# Bien_Quang_Cao_ver2_schematic.net
KiCad netlist of a schematic drawn in Altium Designer
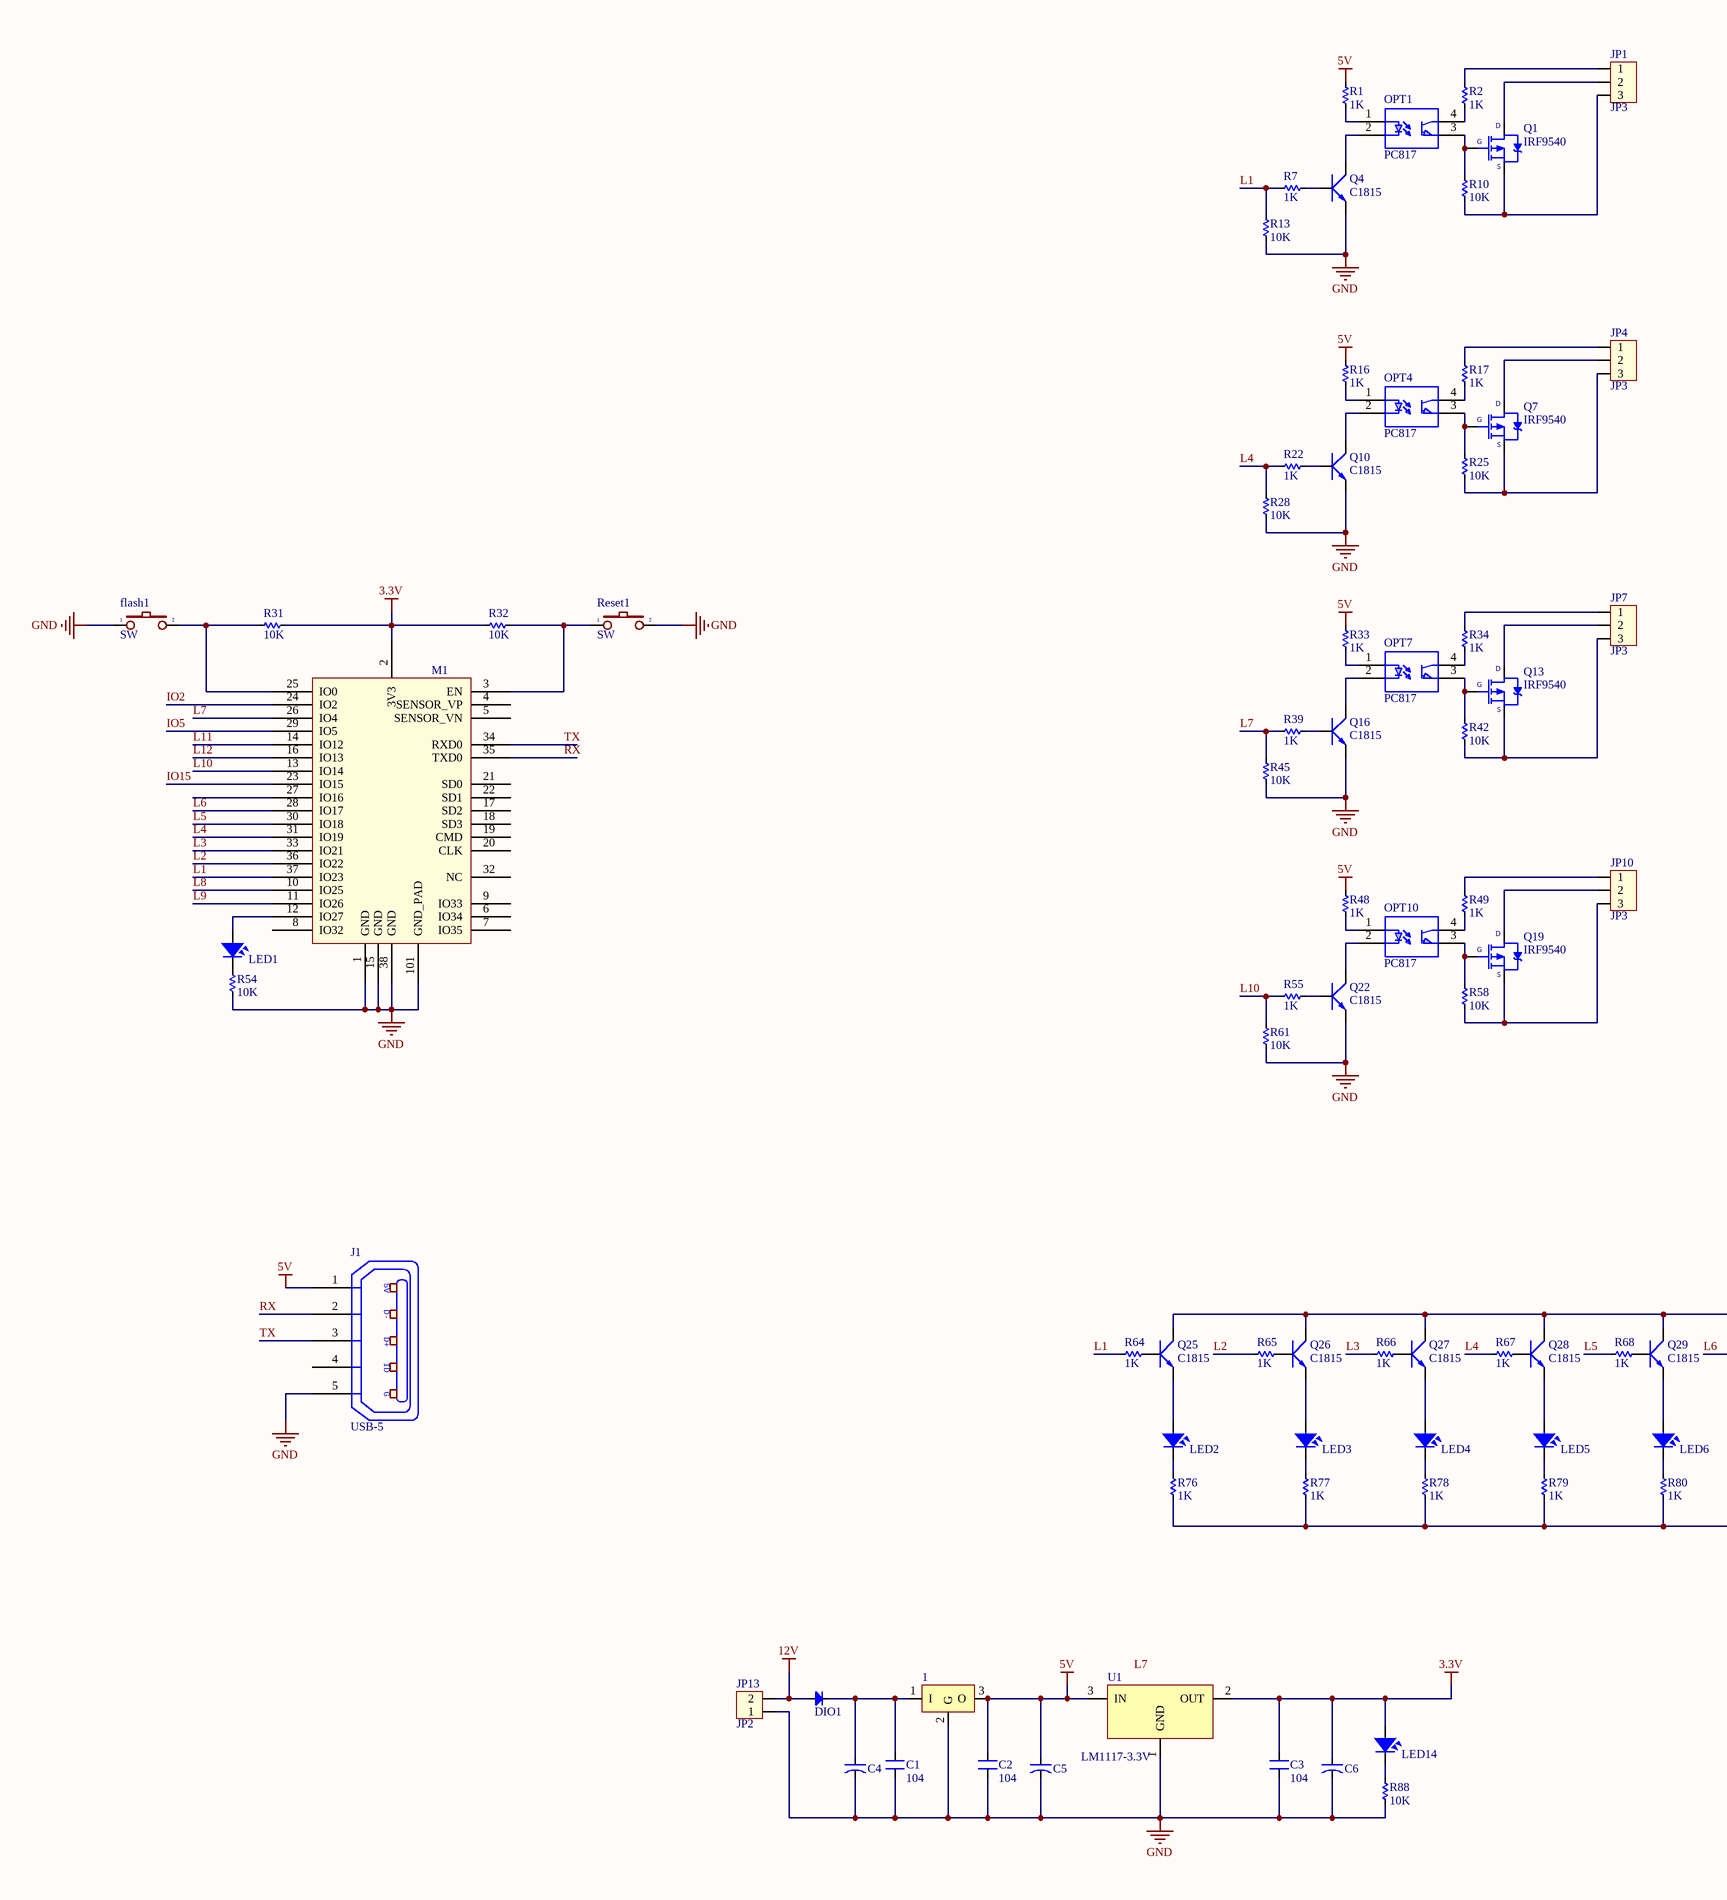
[diagram p0: Bien_Quang_Cao_ver2_schematic.SchDoc, left]
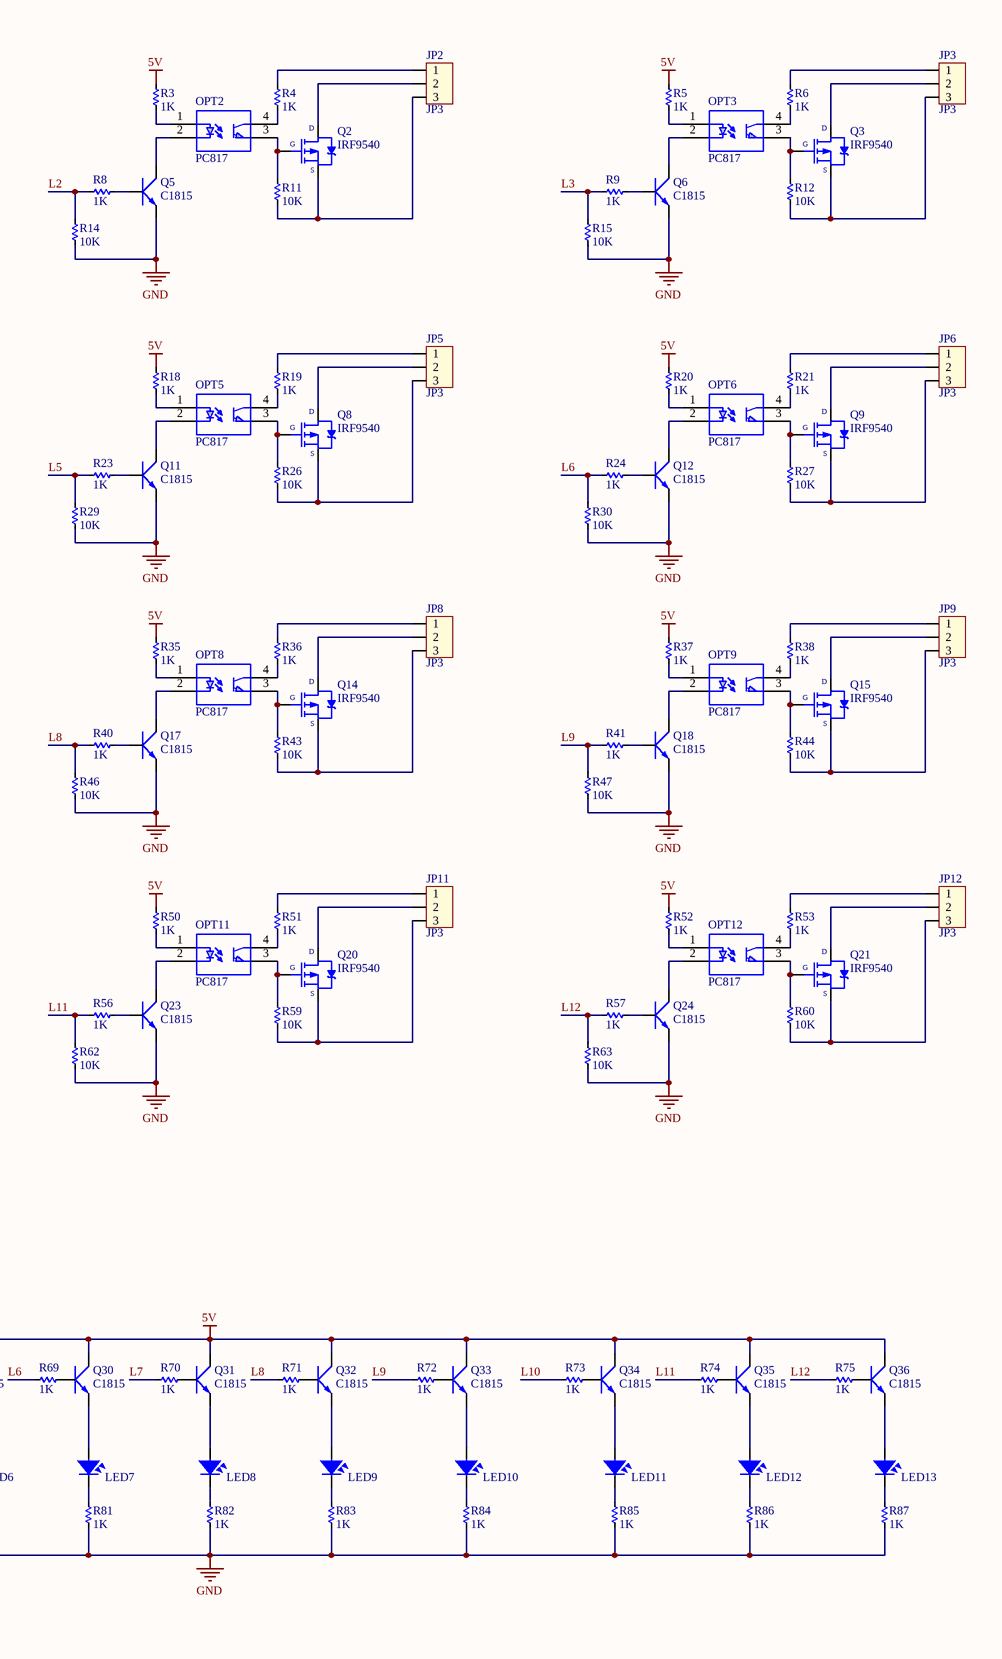
[diagram p1: Bien_Quang_Cao_ver2_schematic.SchDoc, right]

(export (version "E")
  (design (tool "Eeschema 10.0.6"))
  (components
    (comp (ref "1")
      (value "LM78xx")
      (footprint "TO252-123")
      (description "Positive Voltage Regulator")
      (fields (field (name "PUBLISHER") "Altium Limited"))
      (libsource (lib "LIBRARY") (part "LM78xx"))
    )
    (comp (ref "C1")
      (value "104")
      (footprint "SM-CAP-0805")
      (fields (field (name "DESIGNED BY") "VanDungEvn"))
      (libsource (lib "electronicvn-library1") (part "CN"))
    )
    (comp (ref "C2")
      (value "104")
      (footprint "SM-CAP-0805")
      (fields (field (name "DESIGNED BY") "VanDungEvn"))
      (libsource (lib "electronicvn-library1") (part "CN"))
    )
    (comp (ref "C3")
      (value "104")
      (footprint "SM-CAP-0805")
      (fields (field (name "DESIGNED BY") "VanDungEvn"))
      (libsource (lib "electronicvn-library1") (part "CN"))
    )
    (comp (ref "C4")
      (value "CN-ALU-SMD")
      (footprint "CAP-ALU-SMD-5x5.5x1.4")
      (description "Polarized Capacitor (Axial)")
      (fields (field (name "PUBLISHER") "Altium Limited"))
      (libsource (lib "LIBTanCN") (part "CN-ALU-SMD"))
    )
    (comp (ref "C5")
      (value "CN-ALU-SMD")
      (footprint "CAP-ALU-SMD-5x5.5x1.4")
      (description "Polarized Capacitor (Axial)")
      (fields (field (name "PUBLISHER") "Altium Limited"))
      (libsource (lib "LIBTanCN") (part "CN-ALU-SMD"))
    )
    (comp (ref "C6")
      (value "CN-ALU-SMD")
      (footprint "CAP-ALU-SMD-5x5.5x1.4")
      (description "Polarized Capacitor (Axial)")
      (fields (field (name "PUBLISHER") "Altium Limited"))
      (libsource (lib "LIBTanCN") (part "CN-ALU-SMD"))
    )
    (comp (ref "DIO1")
      (value "Diode SMD")
      (footprint "DIO-SMD-106")
      (description "Default Diode")
      (fields (field (name "PUBLISHER") "Altium Limited"))
      (libsource (lib "LIBRARY") (part "Diode SMD"))
    )
    (comp (ref "flash1")
      (value "SW")
      (footprint "SW-DIP1")
      (description "Switch button 2 pin")
      (libsource (lib "LIBRARY") (part "SW2"))
    )
    (comp (ref "J1")
      (value "USB-5")
      (footprint "USB-M1")
      (fields
        (field (name "MANUFACTURER") "FCI")
        (field (name "MANUFACTURER PART NUMBER") "10118193-0001LF")
        (field (name ".CREATOR") "MM")
        (field (name ".CHECKED PCB") "RF")
        (field (name ".CHECKED SCH") "MM")
      )
      (libsource (lib "LIBRARY") (part "USB-5"))
    )
    (comp (ref "JP1")
      (value "JP3")
      (footprint "CON 3/9.5mm - CHAN LECH")
      (description "Connector 3")
      (libsource (lib "Tr.Thoai") (part "Con3"))
    )
    (comp (ref "JP2")
      (value "JP3")
      (footprint "CON 3/9.5mm - CHAN LECH")
      (description "Connector 3")
      (libsource (lib "Tr.Thoai") (part "Con3"))
    )
    (comp (ref "JP3")
      (value "JP3")
      (footprint "CON 3/9.5mm - CHAN LECH")
      (description "Connector 3")
      (libsource (lib "Tr.Thoai") (part "Con3"))
    )
    (comp (ref "JP4")
      (value "JP3")
      (footprint "CON 3/9.5mm - CHAN LECH")
      (description "Connector 3")
      (libsource (lib "Tr.Thoai") (part "Con3"))
    )
    (comp (ref "JP5")
      (value "JP3")
      (footprint "CON 3/9.5mm - CHAN LECH")
      (description "Connector 3")
      (libsource (lib "Tr.Thoai") (part "Con3"))
    )
    (comp (ref "JP6")
      (value "JP3")
      (footprint "CON 3/9.5mm - CHAN LECH")
      (description "Connector 3")
      (libsource (lib "Tr.Thoai") (part "Con3"))
    )
    (comp (ref "JP7")
      (value "JP3")
      (footprint "CON 3/9.5mm - CHAN LECH")
      (description "Connector 3")
      (libsource (lib "Tr.Thoai") (part "Con3"))
    )
    (comp (ref "JP8")
      (value "JP3")
      (footprint "CON 3/9.5mm - CHAN LECH")
      (description "Connector 3")
      (libsource (lib "Tr.Thoai") (part "Con3"))
    )
    (comp (ref "JP9")
      (value "JP3")
      (footprint "CON 3/9.5mm - CHAN LECH")
      (description "Connector 3")
      (libsource (lib "Tr.Thoai") (part "Con3"))
    )
    (comp (ref "JP10")
      (value "JP3")
      (footprint "CON 3/9.5mm - CHAN LECH")
      (description "Connector 3")
      (libsource (lib "Tr.Thoai") (part "Con3"))
    )
    (comp (ref "JP11")
      (value "JP3")
      (footprint "CON 3/9.5mm - CHAN LECH")
      (description "Connector 3")
      (libsource (lib "Tr.Thoai") (part "Con3"))
    )
    (comp (ref "JP12")
      (value "JP3")
      (footprint "CON 3/9.5mm - CHAN LECH")
      (description "Connector 3")
      (libsource (lib "Tr.Thoai") (part "Con3"))
    )
    (comp (ref "JP13")
      (value "JP2")
      (footprint "CON 2/7.62mm")
      (description "Connector 2")
      (libsource (lib "Tr.Thoai") (part "Con2"))
    )
    (comp (ref "LED1") (value "LED") (footprint "LED-0805-Blue") (libsource (lib "LIBRARY") (part "LED SMD")))
    (comp (ref "LED2") (value "LED") (footprint "LED-0805-Blue") (libsource (lib "LIBRARY") (part "LED SMD")))
    (comp (ref "LED3") (value "LED") (footprint "LED-0805-Blue") (libsource (lib "LIBRARY") (part "LED SMD")))
    (comp (ref "LED4") (value "LED") (footprint "LED-0805-Blue") (libsource (lib "LIBRARY") (part "LED SMD")))
    (comp (ref "LED5") (value "LED") (footprint "LED-0805-Blue") (libsource (lib "LIBRARY") (part "LED SMD")))
    (comp (ref "LED6") (value "LED") (footprint "LED-0805-Blue") (libsource (lib "LIBRARY") (part "LED SMD")))
    (comp (ref "LED7") (value "LED") (footprint "LED-0805-Blue") (libsource (lib "LIBRARY") (part "LED SMD")))
    (comp (ref "LED8") (value "LED") (footprint "LED-0805-Blue") (libsource (lib "LIBRARY") (part "LED SMD")))
    (comp (ref "LED9") (value "LED") (footprint "LED-0805-Blue") (libsource (lib "LIBRARY") (part "LED SMD")))
    (comp (ref "LED10")
      (value "LED")
      (footprint "LED-0805-Blue")
      (libsource (lib "LIBRARY") (part "LED SMD"))
    )
    (comp (ref "LED11")
      (value "LED")
      (footprint "LED-0805-Blue")
      (libsource (lib "LIBRARY") (part "LED SMD"))
    )
    (comp (ref "LED12")
      (value "LED")
      (footprint "LED-0805-Blue")
      (libsource (lib "LIBRARY") (part "LED SMD"))
    )
    (comp (ref "LED13")
      (value "LED")
      (footprint "LED-0805-Blue")
      (libsource (lib "LIBRARY") (part "LED SMD"))
    )
    (comp (ref "LED14")
      (value "LED")
      (footprint "LED-0805-Blue")
      (libsource (lib "LIBRARY") (part "LED SMD"))
    )
    (comp (ref "M1")
      (value "ESP32S_Module")
      (footprint "ESP32S")
      (description "Esp-32S")
      (libsource (lib "ESP32S") (part "ESP32S_Module"))
    )
    (comp (ref "OPT1")
      (value "PC817")
      (footprint "DIP-4 SMD")
      (description "OptoAcoplador 4 terminais")
      (libsource (lib "Altium_Library_Brasil") (part "PC817"))
    )
    (comp (ref "OPT2")
      (value "PC817")
      (footprint "DIP-4 SMD")
      (description "OptoAcoplador 4 terminais")
      (libsource (lib "Altium_Library_Brasil") (part "PC817"))
    )
    (comp (ref "OPT3")
      (value "PC817")
      (footprint "DIP-4 SMD")
      (description "OptoAcoplador 4 terminais")
      (libsource (lib "Altium_Library_Brasil") (part "PC817"))
    )
    (comp (ref "OPT4")
      (value "PC817")
      (footprint "DIP-4 SMD")
      (description "OptoAcoplador 4 terminais")
      (libsource (lib "Altium_Library_Brasil") (part "PC817"))
    )
    (comp (ref "OPT5")
      (value "PC817")
      (footprint "DIP-4 SMD")
      (description "OptoAcoplador 4 terminais")
      (libsource (lib "Altium_Library_Brasil") (part "PC817"))
    )
    (comp (ref "OPT6")
      (value "PC817")
      (footprint "DIP-4 SMD")
      (description "OptoAcoplador 4 terminais")
      (libsource (lib "Altium_Library_Brasil") (part "PC817"))
    )
    (comp (ref "OPT7")
      (value "PC817")
      (footprint "DIP-4 SMD")
      (description "OptoAcoplador 4 terminais")
      (libsource (lib "Altium_Library_Brasil") (part "PC817"))
    )
    (comp (ref "OPT8")
      (value "PC817")
      (footprint "DIP-4 SMD")
      (description "OptoAcoplador 4 terminais")
      (libsource (lib "Altium_Library_Brasil") (part "PC817"))
    )
    (comp (ref "OPT9")
      (value "PC817")
      (footprint "DIP-4 SMD")
      (description "OptoAcoplador 4 terminais")
      (libsource (lib "Altium_Library_Brasil") (part "PC817"))
    )
    (comp (ref "OPT10")
      (value "PC817")
      (footprint "DIP-4 SMD")
      (description "OptoAcoplador 4 terminais")
      (libsource (lib "Altium_Library_Brasil") (part "PC817"))
    )
    (comp (ref "OPT11")
      (value "PC817")
      (footprint "DIP-4 SMD")
      (description "OptoAcoplador 4 terminais")
      (libsource (lib "Altium_Library_Brasil") (part "PC817"))
    )
    (comp (ref "OPT12")
      (value "PC817")
      (footprint "DIP-4 SMD")
      (description "OptoAcoplador 4 terminais")
      (libsource (lib "Altium_Library_Brasil") (part "PC817"))
    )
    (comp (ref "Q1")
      (value "IRF9540")
      (footprint "TO247")
      (description "HEXFET P-Channel Power MOSFET")
      (fields (field (name "PUBLISHER") "Altium Limited"))
      (libsource (lib "LIBTanCN") (part "IRF9540"))
    )
    (comp (ref "Q2")
      (value "IRF9540")
      (footprint "TO247")
      (description "HEXFET P-Channel Power MOSFET")
      (fields (field (name "PUBLISHER") "Altium Limited"))
      (libsource (lib "LIBTanCN") (part "IRF9540"))
    )
    (comp (ref "Q3")
      (value "IRF9540")
      (footprint "TO247")
      (description "HEXFET P-Channel Power MOSFET")
      (fields (field (name "PUBLISHER") "Altium Limited"))
      (libsource (lib "LIBTanCN") (part "IRF9540"))
    )
    (comp (ref "Q4")
      (value "C1815")
      (footprint "SOT23B")
      (description "NPN 600mW, ECB")
      (libsource (lib "electronicvn-library1") (part "C1815"))
    )
    (comp (ref "Q5")
      (value "C1815")
      (footprint "SOT23B")
      (description "NPN 600mW, ECB")
      (libsource (lib "electronicvn-library1") (part "C1815"))
    )
    (comp (ref "Q6")
      (value "C1815")
      (footprint "SOT23B")
      (description "NPN 600mW, ECB")
      (libsource (lib "electronicvn-library1") (part "C1815"))
    )
    (comp (ref "Q7")
      (value "IRF9540")
      (footprint "TO247")
      (description "HEXFET P-Channel Power MOSFET")
      (fields (field (name "PUBLISHER") "Altium Limited"))
      (libsource (lib "LIBTanCN") (part "IRF9540"))
    )
    (comp (ref "Q8")
      (value "IRF9540")
      (footprint "TO247")
      (description "HEXFET P-Channel Power MOSFET")
      (fields (field (name "PUBLISHER") "Altium Limited"))
      (libsource (lib "LIBTanCN") (part "IRF9540"))
    )
    (comp (ref "Q9")
      (value "IRF9540")
      (footprint "TO247")
      (description "HEXFET P-Channel Power MOSFET")
      (fields (field (name "PUBLISHER") "Altium Limited"))
      (libsource (lib "LIBTanCN") (part "IRF9540"))
    )
    (comp (ref "Q10")
      (value "C1815")
      (footprint "SOT23B")
      (description "NPN 600mW, ECB")
      (libsource (lib "electronicvn-library1") (part "C1815"))
    )
    (comp (ref "Q11")
      (value "C1815")
      (footprint "SOT23B")
      (description "NPN 600mW, ECB")
      (libsource (lib "electronicvn-library1") (part "C1815"))
    )
    (comp (ref "Q12")
      (value "C1815")
      (footprint "SOT23B")
      (description "NPN 600mW, ECB")
      (libsource (lib "electronicvn-library1") (part "C1815"))
    )
    (comp (ref "Q13")
      (value "IRF9540")
      (footprint "TO247")
      (description "HEXFET P-Channel Power MOSFET")
      (fields (field (name "PUBLISHER") "Altium Limited"))
      (libsource (lib "LIBTanCN") (part "IRF9540"))
    )
    (comp (ref "Q14")
      (value "IRF9540")
      (footprint "TO247")
      (description "HEXFET P-Channel Power MOSFET")
      (fields (field (name "PUBLISHER") "Altium Limited"))
      (libsource (lib "LIBTanCN") (part "IRF9540"))
    )
    (comp (ref "Q15")
      (value "IRF9540")
      (footprint "TO247")
      (description "HEXFET P-Channel Power MOSFET")
      (fields (field (name "PUBLISHER") "Altium Limited"))
      (libsource (lib "LIBTanCN") (part "IRF9540"))
    )
    (comp (ref "Q16")
      (value "C1815")
      (footprint "SOT23B")
      (description "NPN 600mW, ECB")
      (libsource (lib "electronicvn-library1") (part "C1815"))
    )
    (comp (ref "Q17")
      (value "C1815")
      (footprint "SOT23B")
      (description "NPN 600mW, ECB")
      (libsource (lib "electronicvn-library1") (part "C1815"))
    )
    (comp (ref "Q18")
      (value "C1815")
      (footprint "SOT23B")
      (description "NPN 600mW, ECB")
      (libsource (lib "electronicvn-library1") (part "C1815"))
    )
    (comp (ref "Q19")
      (value "IRF9540")
      (footprint "TO247")
      (description "HEXFET P-Channel Power MOSFET")
      (fields (field (name "PUBLISHER") "Altium Limited"))
      (libsource (lib "LIBTanCN") (part "IRF9540"))
    )
    (comp (ref "Q20")
      (value "IRF9540")
      (footprint "TO247")
      (description "HEXFET P-Channel Power MOSFET")
      (fields (field (name "PUBLISHER") "Altium Limited"))
      (libsource (lib "LIBTanCN") (part "IRF9540"))
    )
    (comp (ref "Q21")
      (value "IRF9540")
      (footprint "TO247")
      (description "HEXFET P-Channel Power MOSFET")
      (fields (field (name "PUBLISHER") "Altium Limited"))
      (libsource (lib "LIBTanCN") (part "IRF9540"))
    )
    (comp (ref "Q22")
      (value "C1815")
      (footprint "SOT23B")
      (description "NPN 600mW, ECB")
      (libsource (lib "electronicvn-library1") (part "C1815"))
    )
    (comp (ref "Q23")
      (value "C1815")
      (footprint "SOT23B")
      (description "NPN 600mW, ECB")
      (libsource (lib "electronicvn-library1") (part "C1815"))
    )
    (comp (ref "Q24")
      (value "C1815")
      (footprint "SOT23B")
      (description "NPN 600mW, ECB")
      (libsource (lib "electronicvn-library1") (part "C1815"))
    )
    (comp (ref "Q25")
      (value "C1815")
      (footprint "SOT23B")
      (description "NPN 600mW, ECB")
      (libsource (lib "electronicvn-library1") (part "C1815"))
    )
    (comp (ref "Q26")
      (value "C1815")
      (footprint "SOT23B")
      (description "NPN 600mW, ECB")
      (libsource (lib "electronicvn-library1") (part "C1815"))
    )
    (comp (ref "Q27")
      (value "C1815")
      (footprint "SOT23B")
      (description "NPN 600mW, ECB")
      (libsource (lib "electronicvn-library1") (part "C1815"))
    )
    (comp (ref "Q28")
      (value "C1815")
      (footprint "SOT23B")
      (description "NPN 600mW, ECB")
      (libsource (lib "electronicvn-library1") (part "C1815"))
    )
    (comp (ref "Q29")
      (value "C1815")
      (footprint "SOT23B")
      (description "NPN 600mW, ECB")
      (libsource (lib "electronicvn-library1") (part "C1815"))
    )
    (comp (ref "Q30")
      (value "C1815")
      (footprint "SOT23B")
      (description "NPN 600mW, ECB")
      (libsource (lib "electronicvn-library1") (part "C1815"))
    )
    (comp (ref "Q31")
      (value "C1815")
      (footprint "SOT23B")
      (description "NPN 600mW, ECB")
      (libsource (lib "electronicvn-library1") (part "C1815"))
    )
    (comp (ref "Q32")
      (value "C1815")
      (footprint "SOT23B")
      (description "NPN 600mW, ECB")
      (libsource (lib "electronicvn-library1") (part "C1815"))
    )
    (comp (ref "Q33")
      (value "C1815")
      (footprint "SOT23B")
      (description "NPN 600mW, ECB")
      (libsource (lib "electronicvn-library1") (part "C1815"))
    )
    (comp (ref "Q34")
      (value "C1815")
      (footprint "SOT23B")
      (description "NPN 600mW, ECB")
      (libsource (lib "electronicvn-library1") (part "C1815"))
    )
    (comp (ref "Q35")
      (value "C1815")
      (footprint "SOT23B")
      (description "NPN 600mW, ECB")
      (libsource (lib "electronicvn-library1") (part "C1815"))
    )
    (comp (ref "Q36")
      (value "C1815")
      (footprint "SOT23B")
      (description "NPN 600mW, ECB")
      (libsource (lib "electronicvn-library1") (part "C1815"))
    )
    (comp (ref "R1")
      (value "1K")
      (footprint "RES-SMD-0805")
      (description "Resistor")
      (fields
        (field (name "MANUFACTURER") "Generic Components")
        (field (name "PUBLISHER") "Altium Hobart Technology Centre")
      )
      (libsource (lib "LIBRARY") (part "Res-SMD"))
    )
    (comp (ref "R2")
      (value "1K")
      (footprint "RES-SMD-0805")
      (description "Resistor")
      (fields
        (field (name "MANUFACTURER") "Generic Components")
        (field (name "PUBLISHER") "Altium Hobart Technology Centre")
      )
      (libsource (lib "LIBRARY") (part "Res-SMD"))
    )
    (comp (ref "R3")
      (value "1K")
      (footprint "RES-SMD-0805")
      (description "Resistor")
      (fields
        (field (name "MANUFACTURER") "Generic Components")
        (field (name "PUBLISHER") "Altium Hobart Technology Centre")
      )
      (libsource (lib "LIBRARY") (part "Res-SMD"))
    )
    (comp (ref "R4")
      (value "1K")
      (footprint "RES-SMD-0805")
      (description "Resistor")
      (fields
        (field (name "MANUFACTURER") "Generic Components")
        (field (name "PUBLISHER") "Altium Hobart Technology Centre")
      )
      (libsource (lib "LIBRARY") (part "Res-SMD"))
    )
    (comp (ref "R5")
      (value "1K")
      (footprint "RES-SMD-0805")
      (description "Resistor")
      (fields
        (field (name "MANUFACTURER") "Generic Components")
        (field (name "PUBLISHER") "Altium Hobart Technology Centre")
      )
      (libsource (lib "LIBRARY") (part "Res-SMD"))
    )
    (comp (ref "R6")
      (value "1K")
      (footprint "RES-SMD-0805")
      (description "Resistor")
      (fields
        (field (name "MANUFACTURER") "Generic Components")
        (field (name "PUBLISHER") "Altium Hobart Technology Centre")
      )
      (libsource (lib "LIBRARY") (part "Res-SMD"))
    )
    (comp (ref "R7")
      (value "1K")
      (footprint "RES-SMD-0805")
      (description "Resistor")
      (fields
        (field (name "MANUFACTURER") "Generic Components")
        (field (name "PUBLISHER") "Altium Hobart Technology Centre")
      )
      (libsource (lib "LIBRARY") (part "Res-SMD"))
    )
    (comp (ref "R8")
      (value "1K")
      (footprint "RES-SMD-0805")
      (description "Resistor")
      (fields
        (field (name "MANUFACTURER") "Generic Components")
        (field (name "PUBLISHER") "Altium Hobart Technology Centre")
      )
      (libsource (lib "LIBRARY") (part "Res-SMD"))
    )
    (comp (ref "R9")
      (value "1K")
      (footprint "RES-SMD-0805")
      (description "Resistor")
      (fields
        (field (name "MANUFACTURER") "Generic Components")
        (field (name "PUBLISHER") "Altium Hobart Technology Centre")
      )
      (libsource (lib "LIBRARY") (part "Res-SMD"))
    )
    (comp (ref "R10")
      (value "10K")
      (footprint "RES-SMD-0805")
      (description "Resistor")
      (fields
        (field (name "MANUFACTURER") "Generic Components")
        (field (name "PUBLISHER") "Altium Hobart Technology Centre")
      )
      (libsource (lib "LIBRARY") (part "Res-SMD"))
    )
    (comp (ref "R11")
      (value "10K")
      (footprint "RES-SMD-0805")
      (description "Resistor")
      (fields
        (field (name "MANUFACTURER") "Generic Components")
        (field (name "PUBLISHER") "Altium Hobart Technology Centre")
      )
      (libsource (lib "LIBRARY") (part "Res-SMD"))
    )
    (comp (ref "R12")
      (value "10K")
      (footprint "RES-SMD-0805")
      (description "Resistor")
      (fields
        (field (name "MANUFACTURER") "Generic Components")
        (field (name "PUBLISHER") "Altium Hobart Technology Centre")
      )
      (libsource (lib "LIBRARY") (part "Res-SMD"))
    )
    (comp (ref "R13")
      (value "10K")
      (footprint "RES-SMD-0805")
      (description "Resistor")
      (fields
        (field (name "MANUFACTURER") "Generic Components")
        (field (name "PUBLISHER") "Altium Hobart Technology Centre")
      )
      (libsource (lib "LIBRARY") (part "Res-SMD"))
    )
    (comp (ref "R14")
      (value "10K")
      (footprint "RES-SMD-0805")
      (description "Resistor")
      (fields
        (field (name "MANUFACTURER") "Generic Components")
        (field (name "PUBLISHER") "Altium Hobart Technology Centre")
      )
      (libsource (lib "LIBRARY") (part "Res-SMD"))
    )
    (comp (ref "R15")
      (value "10K")
      (footprint "RES-SMD-0805")
      (description "Resistor")
      (fields
        (field (name "MANUFACTURER") "Generic Components")
        (field (name "PUBLISHER") "Altium Hobart Technology Centre")
      )
      (libsource (lib "LIBRARY") (part "Res-SMD"))
    )
    (comp (ref "R16")
      (value "1K")
      (footprint "RES-SMD-0805")
      (description "Resistor")
      (fields
        (field (name "MANUFACTURER") "Generic Components")
        (field (name "PUBLISHER") "Altium Hobart Technology Centre")
      )
      (libsource (lib "LIBRARY") (part "Res-SMD"))
    )
    (comp (ref "R17")
      (value "1K")
      (footprint "RES-SMD-0805")
      (description "Resistor")
      (fields
        (field (name "MANUFACTURER") "Generic Components")
        (field (name "PUBLISHER") "Altium Hobart Technology Centre")
      )
      (libsource (lib "LIBRARY") (part "Res-SMD"))
    )
    (comp (ref "R18")
      (value "1K")
      (footprint "RES-SMD-0805")
      (description "Resistor")
      (fields
        (field (name "MANUFACTURER") "Generic Components")
        (field (name "PUBLISHER") "Altium Hobart Technology Centre")
      )
      (libsource (lib "LIBRARY") (part "Res-SMD"))
    )
    (comp (ref "R19")
      (value "1K")
      (footprint "RES-SMD-0805")
      (description "Resistor")
      (fields
        (field (name "MANUFACTURER") "Generic Components")
        (field (name "PUBLISHER") "Altium Hobart Technology Centre")
      )
      (libsource (lib "LIBRARY") (part "Res-SMD"))
    )
    (comp (ref "R20")
      (value "1K")
      (footprint "RES-SMD-0805")
      (description "Resistor")
      (fields
        (field (name "MANUFACTURER") "Generic Components")
        (field (name "PUBLISHER") "Altium Hobart Technology Centre")
      )
      (libsource (lib "LIBRARY") (part "Res-SMD"))
    )
    (comp (ref "R21")
      (value "1K")
      (footprint "RES-SMD-0805")
      (description "Resistor")
      (fields
        (field (name "MANUFACTURER") "Generic Components")
        (field (name "PUBLISHER") "Altium Hobart Technology Centre")
      )
      (libsource (lib "LIBRARY") (part "Res-SMD"))
    )
    (comp (ref "R22")
      (value "1K")
      (footprint "RES-SMD-0805")
      (description "Resistor")
      (fields
        (field (name "MANUFACTURER") "Generic Components")
        (field (name "PUBLISHER") "Altium Hobart Technology Centre")
      )
      (libsource (lib "LIBRARY") (part "Res-SMD"))
    )
    (comp (ref "R23")
      (value "1K")
      (footprint "RES-SMD-0805")
      (description "Resistor")
      (fields
        (field (name "MANUFACTURER") "Generic Components")
        (field (name "PUBLISHER") "Altium Hobart Technology Centre")
      )
      (libsource (lib "LIBRARY") (part "Res-SMD"))
    )
    (comp (ref "R24")
      (value "1K")
      (footprint "RES-SMD-0805")
      (description "Resistor")
      (fields
        (field (name "MANUFACTURER") "Generic Components")
        (field (name "PUBLISHER") "Altium Hobart Technology Centre")
      )
      (libsource (lib "LIBRARY") (part "Res-SMD"))
    )
    (comp (ref "R25")
      (value "10K")
      (footprint "RES-SMD-0805")
      (description "Resistor")
      (fields
        (field (name "MANUFACTURER") "Generic Components")
        (field (name "PUBLISHER") "Altium Hobart Technology Centre")
      )
      (libsource (lib "LIBRARY") (part "Res-SMD"))
    )
    (comp (ref "R26")
      (value "10K")
      (footprint "RES-SMD-0805")
      (description "Resistor")
      (fields
        (field (name "MANUFACTURER") "Generic Components")
        (field (name "PUBLISHER") "Altium Hobart Technology Centre")
      )
      (libsource (lib "LIBRARY") (part "Res-SMD"))
    )
    (comp (ref "R27")
      (value "10K")
      (footprint "RES-SMD-0805")
      (description "Resistor")
      (fields
        (field (name "MANUFACTURER") "Generic Components")
        (field (name "PUBLISHER") "Altium Hobart Technology Centre")
      )
      (libsource (lib "LIBRARY") (part "Res-SMD"))
    )
    (comp (ref "R28")
      (value "10K")
      (footprint "RES-SMD-0805")
      (description "Resistor")
      (fields
        (field (name "MANUFACTURER") "Generic Components")
        (field (name "PUBLISHER") "Altium Hobart Technology Centre")
      )
      (libsource (lib "LIBRARY") (part "Res-SMD"))
    )
    (comp (ref "R29")
      (value "10K")
      (footprint "RES-SMD-0805")
      (description "Resistor")
      (fields
        (field (name "MANUFACTURER") "Generic Components")
        (field (name "PUBLISHER") "Altium Hobart Technology Centre")
      )
      (libsource (lib "LIBRARY") (part "Res-SMD"))
    )
    (comp (ref "R30")
      (value "10K")
      (footprint "RES-SMD-0805")
      (description "Resistor")
      (fields
        (field (name "MANUFACTURER") "Generic Components")
        (field (name "PUBLISHER") "Altium Hobart Technology Centre")
      )
      (libsource (lib "LIBRARY") (part "Res-SMD"))
    )
    (comp (ref "R31")
      (value "10K")
      (footprint "RES-SMD-0805")
      (description "Resistor")
      (fields
        (field (name "MANUFACTURER") "Generic Components")
        (field (name "PUBLISHER") "Altium Hobart Technology Centre")
      )
      (libsource (lib "LIBRARY") (part "Res-SMD"))
    )
    (comp (ref "R32")
      (value "10K")
      (footprint "RES-SMD-0805")
      (description "Resistor")
      (fields
        (field (name "MANUFACTURER") "Generic Components")
        (field (name "PUBLISHER") "Altium Hobart Technology Centre")
      )
      (libsource (lib "LIBRARY") (part "Res-SMD"))
    )
    (comp (ref "R33")
      (value "1K")
      (footprint "RES-SMD-0805")
      (description "Resistor")
      (fields
        (field (name "MANUFACTURER") "Generic Components")
        (field (name "PUBLISHER") "Altium Hobart Technology Centre")
      )
      (libsource (lib "LIBRARY") (part "Res-SMD"))
    )
    (comp (ref "R34")
      (value "1K")
      (footprint "RES-SMD-0805")
      (description "Resistor")
      (fields
        (field (name "MANUFACTURER") "Generic Components")
        (field (name "PUBLISHER") "Altium Hobart Technology Centre")
      )
      (libsource (lib "LIBRARY") (part "Res-SMD"))
    )
    (comp (ref "R35")
      (value "1K")
      (footprint "RES-SMD-0805")
      (description "Resistor")
      (fields
        (field (name "MANUFACTURER") "Generic Components")
        (field (name "PUBLISHER") "Altium Hobart Technology Centre")
      )
      (libsource (lib "LIBRARY") (part "Res-SMD"))
    )
    (comp (ref "R36")
      (value "1K")
      (footprint "RES-SMD-0805")
      (description "Resistor")
      (fields
        (field (name "MANUFACTURER") "Generic Components")
        (field (name "PUBLISHER") "Altium Hobart Technology Centre")
      )
      (libsource (lib "LIBRARY") (part "Res-SMD"))
    )
    (comp (ref "R37")
      (value "1K")
      (footprint "RES-SMD-0805")
      (description "Resistor")
      (fields
        (field (name "MANUFACTURER") "Generic Components")
        (field (name "PUBLISHER") "Altium Hobart Technology Centre")
      )
      (libsource (lib "LIBRARY") (part "Res-SMD"))
    )
    (comp (ref "R38")
      (value "1K")
      (footprint "RES-SMD-0805")
      (description "Resistor")
      (fields
        (field (name "MANUFACTURER") "Generic Components")
        (field (name "PUBLISHER") "Altium Hobart Technology Centre")
      )
      (libsource (lib "LIBRARY") (part "Res-SMD"))
    )
    (comp (ref "R39")
      (value "1K")
      (footprint "RES-SMD-0805")
      (description "Resistor")
      (fields
        (field (name "MANUFACTURER") "Generic Components")
        (field (name "PUBLISHER") "Altium Hobart Technology Centre")
      )
      (libsource (lib "LIBRARY") (part "Res-SMD"))
    )
    (comp (ref "R40")
      (value "1K")
      (footprint "RES-SMD-0805")
      (description "Resistor")
      (fields
        (field (name "MANUFACTURER") "Generic Components")
        (field (name "PUBLISHER") "Altium Hobart Technology Centre")
      )
      (libsource (lib "LIBRARY") (part "Res-SMD"))
    )
    (comp (ref "R41")
      (value "1K")
      (footprint "RES-SMD-0805")
      (description "Resistor")
      (fields
        (field (name "MANUFACTURER") "Generic Components")
        (field (name "PUBLISHER") "Altium Hobart Technology Centre")
      )
      (libsource (lib "LIBRARY") (part "Res-SMD"))
    )
    (comp (ref "R42")
      (value "10K")
      (footprint "RES-SMD-0805")
      (description "Resistor")
      (fields
        (field (name "MANUFACTURER") "Generic Components")
        (field (name "PUBLISHER") "Altium Hobart Technology Centre")
      )
      (libsource (lib "LIBRARY") (part "Res-SMD"))
    )
    (comp (ref "R43")
      (value "10K")
      (footprint "RES-SMD-0805")
      (description "Resistor")
      (fields
        (field (name "MANUFACTURER") "Generic Components")
        (field (name "PUBLISHER") "Altium Hobart Technology Centre")
      )
      (libsource (lib "LIBRARY") (part "Res-SMD"))
    )
    (comp (ref "R44")
      (value "10K")
      (footprint "RES-SMD-0805")
      (description "Resistor")
      (fields
        (field (name "MANUFACTURER") "Generic Components")
        (field (name "PUBLISHER") "Altium Hobart Technology Centre")
      )
      (libsource (lib "LIBRARY") (part "Res-SMD"))
    )
    (comp (ref "R45")
      (value "10K")
      (footprint "RES-SMD-0805")
      (description "Resistor")
      (fields
        (field (name "MANUFACTURER") "Generic Components")
        (field (name "PUBLISHER") "Altium Hobart Technology Centre")
      )
      (libsource (lib "LIBRARY") (part "Res-SMD"))
    )
    (comp (ref "R46")
      (value "10K")
      (footprint "RES-SMD-0805")
      (description "Resistor")
      (fields
        (field (name "MANUFACTURER") "Generic Components")
        (field (name "PUBLISHER") "Altium Hobart Technology Centre")
      )
      (libsource (lib "LIBRARY") (part "Res-SMD"))
    )
    (comp (ref "R47")
      (value "10K")
      (footprint "RES-SMD-0805")
      (description "Resistor")
      (fields
        (field (name "MANUFACTURER") "Generic Components")
        (field (name "PUBLISHER") "Altium Hobart Technology Centre")
      )
      (libsource (lib "LIBRARY") (part "Res-SMD"))
    )
    (comp (ref "R48")
      (value "1K")
      (footprint "RES-SMD-0805")
      (description "Resistor")
      (fields
        (field (name "MANUFACTURER") "Generic Components")
        (field (name "PUBLISHER") "Altium Hobart Technology Centre")
      )
      (libsource (lib "LIBRARY") (part "Res-SMD"))
    )
    (comp (ref "R49")
      (value "1K")
      (footprint "RES-SMD-0805")
      (description "Resistor")
      (fields
        (field (name "MANUFACTURER") "Generic Components")
        (field (name "PUBLISHER") "Altium Hobart Technology Centre")
      )
      (libsource (lib "LIBRARY") (part "Res-SMD"))
    )
    (comp (ref "R50")
      (value "1K")
      (footprint "RES-SMD-0805")
      (description "Resistor")
      (fields
        (field (name "MANUFACTURER") "Generic Components")
        (field (name "PUBLISHER") "Altium Hobart Technology Centre")
      )
      (libsource (lib "LIBRARY") (part "Res-SMD"))
    )
    (comp (ref "R51")
      (value "1K")
      (footprint "RES-SMD-0805")
      (description "Resistor")
      (fields
        (field (name "MANUFACTURER") "Generic Components")
        (field (name "PUBLISHER") "Altium Hobart Technology Centre")
      )
      (libsource (lib "LIBRARY") (part "Res-SMD"))
    )
    (comp (ref "R52")
      (value "1K")
      (footprint "RES-SMD-0805")
      (description "Resistor")
      (fields
        (field (name "MANUFACTURER") "Generic Components")
        (field (name "PUBLISHER") "Altium Hobart Technology Centre")
      )
      (libsource (lib "LIBRARY") (part "Res-SMD"))
    )
    (comp (ref "R53")
      (value "1K")
      (footprint "RES-SMD-0805")
      (description "Resistor")
      (fields
        (field (name "MANUFACTURER") "Generic Components")
        (field (name "PUBLISHER") "Altium Hobart Technology Centre")
      )
      (libsource (lib "LIBRARY") (part "Res-SMD"))
    )
    (comp (ref "R54")
      (value "10K")
      (footprint "RES-SMD-0805")
      (description "Resistor")
      (fields
        (field (name "MANUFACTURER") "Generic Components")
        (field (name "PUBLISHER") "Altium Hobart Technology Centre")
      )
      (libsource (lib "LIBRARY") (part "Res-SMD"))
    )
    (comp (ref "R55")
      (value "1K")
      (footprint "RES-SMD-0805")
      (description "Resistor")
      (fields
        (field (name "MANUFACTURER") "Generic Components")
        (field (name "PUBLISHER") "Altium Hobart Technology Centre")
      )
      (libsource (lib "LIBRARY") (part "Res-SMD"))
    )
    (comp (ref "R56")
      (value "1K")
      (footprint "RES-SMD-0805")
      (description "Resistor")
      (fields
        (field (name "MANUFACTURER") "Generic Components")
        (field (name "PUBLISHER") "Altium Hobart Technology Centre")
      )
      (libsource (lib "LIBRARY") (part "Res-SMD"))
    )
    (comp (ref "R57")
      (value "1K")
      (footprint "RES-SMD-0805")
      (description "Resistor")
      (fields
        (field (name "MANUFACTURER") "Generic Components")
        (field (name "PUBLISHER") "Altium Hobart Technology Centre")
      )
      (libsource (lib "LIBRARY") (part "Res-SMD"))
    )
    (comp (ref "R58")
      (value "10K")
      (footprint "RES-SMD-0805")
      (description "Resistor")
      (fields
        (field (name "MANUFACTURER") "Generic Components")
        (field (name "PUBLISHER") "Altium Hobart Technology Centre")
      )
      (libsource (lib "LIBRARY") (part "Res-SMD"))
    )
    (comp (ref "R59")
      (value "10K")
      (footprint "RES-SMD-0805")
      (description "Resistor")
      (fields
        (field (name "MANUFACTURER") "Generic Components")
        (field (name "PUBLISHER") "Altium Hobart Technology Centre")
      )
      (libsource (lib "LIBRARY") (part "Res-SMD"))
    )
    (comp (ref "R60")
      (value "10K")
      (footprint "RES-SMD-0805")
      (description "Resistor")
      (fields
        (field (name "MANUFACTURER") "Generic Components")
        (field (name "PUBLISHER") "Altium Hobart Technology Centre")
      )
      (libsource (lib "LIBRARY") (part "Res-SMD"))
    )
    (comp (ref "R61")
      (value "10K")
      (footprint "RES-SMD-0805")
      (description "Resistor")
      (fields
        (field (name "MANUFACTURER") "Generic Components")
        (field (name "PUBLISHER") "Altium Hobart Technology Centre")
      )
      (libsource (lib "LIBRARY") (part "Res-SMD"))
    )
    (comp (ref "R62")
      (value "10K")
      (footprint "RES-SMD-0805")
      (description "Resistor")
      (fields
        (field (name "MANUFACTURER") "Generic Components")
        (field (name "PUBLISHER") "Altium Hobart Technology Centre")
      )
      (libsource (lib "LIBRARY") (part "Res-SMD"))
    )
    (comp (ref "R63")
      (value "10K")
      (footprint "RES-SMD-0805")
      (description "Resistor")
      (fields
        (field (name "MANUFACTURER") "Generic Components")
        (field (name "PUBLISHER") "Altium Hobart Technology Centre")
      )
      (libsource (lib "LIBRARY") (part "Res-SMD"))
    )
    (comp (ref "R64")
      (value "1K")
      (footprint "RES-SMD-0805")
      (description "Resistor")
      (fields
        (field (name "MANUFACTURER") "Generic Components")
        (field (name "PUBLISHER") "Altium Hobart Technology Centre")
      )
      (libsource (lib "LIBRARY") (part "Res-SMD"))
    )
    (comp (ref "R65")
      (value "1K")
      (footprint "RES-SMD-0805")
      (description "Resistor")
      (fields
        (field (name "MANUFACTURER") "Generic Components")
        (field (name "PUBLISHER") "Altium Hobart Technology Centre")
      )
      (libsource (lib "LIBRARY") (part "Res-SMD"))
    )
    (comp (ref "R66")
      (value "1K")
      (footprint "RES-SMD-0805")
      (description "Resistor")
      (fields
        (field (name "MANUFACTURER") "Generic Components")
        (field (name "PUBLISHER") "Altium Hobart Technology Centre")
      )
      (libsource (lib "LIBRARY") (part "Res-SMD"))
    )
    (comp (ref "R67")
      (value "1K")
      (footprint "RES-SMD-0805")
      (description "Resistor")
      (fields
        (field (name "MANUFACTURER") "Generic Components")
        (field (name "PUBLISHER") "Altium Hobart Technology Centre")
      )
      (libsource (lib "LIBRARY") (part "Res-SMD"))
    )
    (comp (ref "R68")
      (value "1K")
      (footprint "RES-SMD-0805")
      (description "Resistor")
      (fields
        (field (name "MANUFACTURER") "Generic Components")
        (field (name "PUBLISHER") "Altium Hobart Technology Centre")
      )
      (libsource (lib "LIBRARY") (part "Res-SMD"))
    )
    (comp (ref "R69")
      (value "1K")
      (footprint "RES-SMD-0805")
      (description "Resistor")
      (fields
        (field (name "MANUFACTURER") "Generic Components")
        (field (name "PUBLISHER") "Altium Hobart Technology Centre")
      )
      (libsource (lib "LIBRARY") (part "Res-SMD"))
    )
    (comp (ref "R70")
      (value "1K")
      (footprint "RES-SMD-0805")
      (description "Resistor")
      (fields
        (field (name "MANUFACTURER") "Generic Components")
        (field (name "PUBLISHER") "Altium Hobart Technology Centre")
      )
      (libsource (lib "LIBRARY") (part "Res-SMD"))
    )
    (comp (ref "R71")
      (value "1K")
      (footprint "RES-SMD-0805")
      (description "Resistor")
      (fields
        (field (name "MANUFACTURER") "Generic Components")
        (field (name "PUBLISHER") "Altium Hobart Technology Centre")
      )
      (libsource (lib "LIBRARY") (part "Res-SMD"))
    )
    (comp (ref "R72")
      (value "1K")
      (footprint "RES-SMD-0805")
      (description "Resistor")
      (fields
        (field (name "MANUFACTURER") "Generic Components")
        (field (name "PUBLISHER") "Altium Hobart Technology Centre")
      )
      (libsource (lib "LIBRARY") (part "Res-SMD"))
    )
    (comp (ref "R73")
      (value "1K")
      (footprint "RES-SMD-0805")
      (description "Resistor")
      (fields
        (field (name "MANUFACTURER") "Generic Components")
        (field (name "PUBLISHER") "Altium Hobart Technology Centre")
      )
      (libsource (lib "LIBRARY") (part "Res-SMD"))
    )
    (comp (ref "R74")
      (value "1K")
      (footprint "RES-SMD-0805")
      (description "Resistor")
      (fields
        (field (name "MANUFACTURER") "Generic Components")
        (field (name "PUBLISHER") "Altium Hobart Technology Centre")
      )
      (libsource (lib "LIBRARY") (part "Res-SMD"))
    )
    (comp (ref "R75")
      (value "1K")
      (footprint "RES-SMD-0805")
      (description "Resistor")
      (fields
        (field (name "MANUFACTURER") "Generic Components")
        (field (name "PUBLISHER") "Altium Hobart Technology Centre")
      )
      (libsource (lib "LIBRARY") (part "Res-SMD"))
    )
    (comp (ref "R76")
      (value "1K")
      (footprint "RES-SMD-0805")
      (description "Resistor")
      (fields
        (field (name "MANUFACTURER") "Generic Components")
        (field (name "PUBLISHER") "Altium Hobart Technology Centre")
      )
      (libsource (lib "LIBRARY") (part "Res-SMD"))
    )
    (comp (ref "R77")
      (value "1K")
      (footprint "RES-SMD-0805")
      (description "Resistor")
      (fields
        (field (name "MANUFACTURER") "Generic Components")
        (field (name "PUBLISHER") "Altium Hobart Technology Centre")
      )
      (libsource (lib "LIBRARY") (part "Res-SMD"))
    )
    (comp (ref "R78")
      (value "1K")
      (footprint "RES-SMD-0805")
      (description "Resistor")
      (fields
        (field (name "MANUFACTURER") "Generic Components")
        (field (name "PUBLISHER") "Altium Hobart Technology Centre")
      )
      (libsource (lib "LIBRARY") (part "Res-SMD"))
    )
    (comp (ref "R79")
      (value "1K")
      (footprint "RES-SMD-0805")
      (description "Resistor")
      (fields
        (field (name "MANUFACTURER") "Generic Components")
        (field (name "PUBLISHER") "Altium Hobart Technology Centre")
      )
      (libsource (lib "LIBRARY") (part "Res-SMD"))
    )
    (comp (ref "R80")
      (value "1K")
      (footprint "RES-SMD-0805")
      (description "Resistor")
      (fields
        (field (name "MANUFACTURER") "Generic Components")
        (field (name "PUBLISHER") "Altium Hobart Technology Centre")
      )
      (libsource (lib "LIBRARY") (part "Res-SMD"))
    )
    (comp (ref "R81")
      (value "1K")
      (footprint "RES-SMD-0805")
      (description "Resistor")
      (fields
        (field (name "MANUFACTURER") "Generic Components")
        (field (name "PUBLISHER") "Altium Hobart Technology Centre")
      )
      (libsource (lib "LIBRARY") (part "Res-SMD"))
    )
    (comp (ref "R82")
      (value "1K")
      (footprint "RES-SMD-0805")
      (description "Resistor")
      (fields
        (field (name "MANUFACTURER") "Generic Components")
        (field (name "PUBLISHER") "Altium Hobart Technology Centre")
      )
      (libsource (lib "LIBRARY") (part "Res-SMD"))
    )
    (comp (ref "R83")
      (value "1K")
      (footprint "RES-SMD-0805")
      (description "Resistor")
      (fields
        (field (name "MANUFACTURER") "Generic Components")
        (field (name "PUBLISHER") "Altium Hobart Technology Centre")
      )
      (libsource (lib "LIBRARY") (part "Res-SMD"))
    )
    (comp (ref "R84")
      (value "1K")
      (footprint "RES-SMD-0805")
      (description "Resistor")
      (fields
        (field (name "MANUFACTURER") "Generic Components")
        (field (name "PUBLISHER") "Altium Hobart Technology Centre")
      )
      (libsource (lib "LIBRARY") (part "Res-SMD"))
    )
    (comp (ref "R85")
      (value "1K")
      (footprint "RES-SMD-0805")
      (description "Resistor")
      (fields
        (field (name "MANUFACTURER") "Generic Components")
        (field (name "PUBLISHER") "Altium Hobart Technology Centre")
      )
      (libsource (lib "LIBRARY") (part "Res-SMD"))
    )
    (comp (ref "R86")
      (value "1K")
      (footprint "RES-SMD-0805")
      (description "Resistor")
      (fields
        (field (name "MANUFACTURER") "Generic Components")
        (field (name "PUBLISHER") "Altium Hobart Technology Centre")
      )
      (libsource (lib "LIBRARY") (part "Res-SMD"))
    )
    (comp (ref "R87")
      (value "1K")
      (footprint "RES-SMD-0805")
      (description "Resistor")
      (fields
        (field (name "MANUFACTURER") "Generic Components")
        (field (name "PUBLISHER") "Altium Hobart Technology Centre")
      )
      (libsource (lib "LIBRARY") (part "Res-SMD"))
    )
    (comp (ref "R88")
      (value "10K")
      (footprint "RES-SMD-0805")
      (description "Resistor")
      (fields
        (field (name "MANUFACTURER") "Generic Components")
        (field (name "PUBLISHER") "Altium Hobart Technology Centre")
      )
      (libsource (lib "LIBRARY") (part "Res-SMD"))
    )
    (comp (ref "Reset1")
      (value "SW")
      (footprint "SW1-SMD")
      (description "Switch button 2 pin")
      (libsource (lib "LIBRARY") (part "SW2"))
    )
    (comp (ref "U1")
      (value "LM1117-3.3V")
      (footprint "SOT223")
      (description "800mA Low-Dropout Linear Regulator")
      (fields (field (name "CREATOR") "Nguyen Ba Bien"))
      (libsource (lib "LIBRARY") (part "LM1117"))
    )
  )
  (nets
    (net (code "1") (name "/IO2") (class "Default")
      (node (ref "M1") (pin "24") (pinfunction "IO2_24") (pintype "passive"))
    )
    (net (code "2") (name "/IO5") (class "Default")
      (node (ref "M1") (pin "29") (pinfunction "IO5_29") (pintype "passive"))
    )
    (net (code "3") (name "/IO15") (class "Default")
      (node (ref "M1") (pin "23") (pinfunction "IO15_23") (pintype "passive"))
    )
    (net (code "4") (name "/L1") (class "Default")
      (node (ref "M1") (pin "37") (pinfunction "IO23_37") (pintype "passive"))
      (node (ref "R13") (pin "2") (pinfunction "2_2") (pintype "passive"))
      (node (ref "R64") (pin "1") (pinfunction "1_1") (pintype "passive"))
      (node (ref "R7") (pin "1") (pinfunction "1_1") (pintype "passive"))
    )
    (net (code "5") (name "/L2") (class "Default")
      (node (ref "M1") (pin "36") (pinfunction "IO22_36") (pintype "passive"))
      (node (ref "R14") (pin "2") (pinfunction "2_2") (pintype "passive"))
      (node (ref "R65") (pin "1") (pinfunction "1_1") (pintype "passive"))
      (node (ref "R8") (pin "1") (pinfunction "1_1") (pintype "passive"))
    )
    (net (code "6") (name "/L3") (class "Default")
      (node (ref "M1") (pin "33") (pinfunction "IO21_33") (pintype "passive"))
      (node (ref "R15") (pin "2") (pinfunction "2_2") (pintype "passive"))
      (node (ref "R66") (pin "1") (pinfunction "1_1") (pintype "passive"))
      (node (ref "R9") (pin "1") (pinfunction "1_1") (pintype "passive"))
    )
    (net (code "7") (name "/L4") (class "Default")
      (node (ref "M1") (pin "31") (pinfunction "IO19_31") (pintype "passive"))
      (node (ref "R22") (pin "1") (pinfunction "1_1") (pintype "passive"))
      (node (ref "R28") (pin "2") (pinfunction "2_2") (pintype "passive"))
      (node (ref "R67") (pin "1") (pinfunction "1_1") (pintype "passive"))
    )
    (net (code "8") (name "/L5") (class "Default")
      (node (ref "M1") (pin "30") (pinfunction "IO18_30") (pintype "passive"))
      (node (ref "R23") (pin "1") (pinfunction "1_1") (pintype "passive"))
      (node (ref "R29") (pin "2") (pinfunction "2_2") (pintype "passive"))
      (node (ref "R68") (pin "1") (pinfunction "1_1") (pintype "passive"))
    )
    (net (code "9") (name "/L6") (class "Default")
      (node (ref "M1") (pin "28") (pinfunction "IO17_28") (pintype "passive"))
      (node (ref "R24") (pin "1") (pinfunction "1_1") (pintype "passive"))
      (node (ref "R30") (pin "2") (pinfunction "2_2") (pintype "passive"))
      (node (ref "R69") (pin "1") (pinfunction "1_1") (pintype "passive"))
    )
    (net (code "10") (name "/L7") (class "Default")
      (node (ref "M1") (pin "26") (pinfunction "IO4_26") (pintype "passive"))
      (node (ref "R39") (pin "1") (pinfunction "1_1") (pintype "passive"))
      (node (ref "R45") (pin "2") (pinfunction "2_2") (pintype "passive"))
      (node (ref "R70") (pin "1") (pinfunction "1_1") (pintype "passive"))
    )
    (net (code "11") (name "/L8") (class "Default")
      (node (ref "M1") (pin "10") (pinfunction "IO25_10") (pintype "passive"))
      (node (ref "R40") (pin "1") (pinfunction "1_1") (pintype "passive"))
      (node (ref "R46") (pin "2") (pinfunction "2_2") (pintype "passive"))
      (node (ref "R71") (pin "1") (pinfunction "1_1") (pintype "passive"))
    )
    (net (code "12") (name "/L9") (class "Default")
      (node (ref "M1") (pin "11") (pinfunction "IO26_11") (pintype "passive"))
      (node (ref "R41") (pin "1") (pinfunction "1_1") (pintype "passive"))
      (node (ref "R47") (pin "2") (pinfunction "2_2") (pintype "passive"))
      (node (ref "R72") (pin "1") (pinfunction "1_1") (pintype "passive"))
    )
    (net (code "13") (name "/L10") (class "Default")
      (node (ref "M1") (pin "13") (pinfunction "IO14_13") (pintype "passive"))
      (node (ref "R55") (pin "1") (pinfunction "1_1") (pintype "passive"))
      (node (ref "R61") (pin "2") (pinfunction "2_2") (pintype "passive"))
      (node (ref "R73") (pin "1") (pinfunction "1_1") (pintype "passive"))
    )
    (net (code "14") (name "/L11") (class "Default")
      (node (ref "M1") (pin "14") (pinfunction "IO12_14") (pintype "passive"))
      (node (ref "R56") (pin "1") (pinfunction "1_1") (pintype "passive"))
      (node (ref "R62") (pin "2") (pinfunction "2_2") (pintype "passive"))
      (node (ref "R74") (pin "1") (pinfunction "1_1") (pintype "passive"))
    )
    (net (code "15") (name "/L12") (class "Default")
      (node (ref "M1") (pin "16") (pinfunction "IO13_16") (pintype "passive"))
      (node (ref "R57") (pin "1") (pinfunction "1_1") (pintype "passive"))
      (node (ref "R63") (pin "2") (pinfunction "2_2") (pintype "passive"))
      (node (ref "R75") (pin "1") (pinfunction "1_1") (pintype "passive"))
    )
    (net (code "16") (name "/RX") (class "Default")
      (node (ref "J1") (pin "2") (pinfunction "P2_2") (pintype "passive"))
      (node (ref "M1") (pin "35") (pinfunction "TXD0_35") (pintype "passive"))
    )
    (net (code "17") (name "/TX") (class "Default")
      (node (ref "J1") (pin "3") (pinfunction "P3_3") (pintype "passive"))
      (node (ref "M1") (pin "34") (pinfunction "RXD0_34") (pintype "passive"))
    )
    (net (code "18") (name "3.3V") (class "Default")
      (node (ref "C3") (pin "2") (pinfunction "2_2") (pintype "passive"))
      (node (ref "C6") (pin "1") (pinfunction "1_1") (pintype "passive"))
      (node (ref "LED14") (pin "1") (pinfunction "1_1") (pintype "passive"))
      (node (ref "M1") (pin "2") (pinfunction "3V3_2") (pintype "power_in"))
      (node (ref "R31") (pin "2") (pinfunction "2_2") (pintype "passive"))
      (node (ref "R32") (pin "1") (pinfunction "1_1") (pintype "passive"))
      (node (ref "U1") (pin "2") (pinfunction "OUT_2") (pintype "passive"))
    )
    (net (code "19") (name "5V") (class "Default")
      (node (ref "1") (pin "3") (pinfunction "O_3") (pintype "power_in"))
      (node (ref "C2") (pin "2") (pinfunction "2_2") (pintype "passive"))
      (node (ref "C5") (pin "1") (pinfunction "1_1") (pintype "passive"))
      (node (ref "J1") (pin "1") (pinfunction "P1_1") (pintype "passive"))
      (node (ref "Q25") (pin "2") (pinfunction "C_2") (pintype "passive"))
      (node (ref "Q26") (pin "2") (pinfunction "C_2") (pintype "passive"))
      (node (ref "Q27") (pin "2") (pinfunction "C_2") (pintype "passive"))
      (node (ref "Q28") (pin "2") (pinfunction "C_2") (pintype "passive"))
      (node (ref "Q29") (pin "2") (pinfunction "C_2") (pintype "passive"))
      (node (ref "Q30") (pin "2") (pinfunction "C_2") (pintype "passive"))
      (node (ref "Q31") (pin "2") (pinfunction "C_2") (pintype "passive"))
      (node (ref "Q32") (pin "2") (pinfunction "C_2") (pintype "passive"))
      (node (ref "Q33") (pin "2") (pinfunction "C_2") (pintype "passive"))
      (node (ref "Q34") (pin "2") (pinfunction "C_2") (pintype "passive"))
      (node (ref "Q35") (pin "2") (pinfunction "C_2") (pintype "passive"))
      (node (ref "Q36") (pin "2") (pinfunction "C_2") (pintype "passive"))
      (node (ref "R1") (pin "2") (pinfunction "2_2") (pintype "passive"))
      (node (ref "R16") (pin "2") (pinfunction "2_2") (pintype "passive"))
      (node (ref "R18") (pin "2") (pinfunction "2_2") (pintype "passive"))
      (node (ref "R20") (pin "2") (pinfunction "2_2") (pintype "passive"))
      (node (ref "R3") (pin "2") (pinfunction "2_2") (pintype "passive"))
      (node (ref "R33") (pin "2") (pinfunction "2_2") (pintype "passive"))
      (node (ref "R35") (pin "2") (pinfunction "2_2") (pintype "passive"))
      (node (ref "R37") (pin "2") (pinfunction "2_2") (pintype "passive"))
      (node (ref "R48") (pin "2") (pinfunction "2_2") (pintype "passive"))
      (node (ref "R5") (pin "2") (pinfunction "2_2") (pintype "passive"))
      (node (ref "R50") (pin "2") (pinfunction "2_2") (pintype "passive"))
      (node (ref "R52") (pin "2") (pinfunction "2_2") (pintype "passive"))
      (node (ref "U1") (pin "3") (pinfunction "IN_3") (pintype "passive"))
    )
    (net (code "20") (name "12V") (class "Default")
      (node (ref "DIO1") (pin "1") (pinfunction "A_1") (pintype "passive"))
      (node (ref "JP13") (pin "2") (pinfunction "2_2") (pintype "passive"))
    )
    (net (code "21") (name "GND") (class "Default")
      (node (ref "1") (pin "2") (pinfunction "G_2") (pintype "power_in"))
      (node (ref "C1") (pin "1") (pinfunction "1_1") (pintype "passive"))
      (node (ref "C2") (pin "1") (pinfunction "1_1") (pintype "passive"))
      (node (ref "C3") (pin "1") (pinfunction "1_1") (pintype "passive"))
      (node (ref "C4") (pin "2") (pinfunction "2_2") (pintype "passive"))
      (node (ref "C5") (pin "2") (pinfunction "2_2") (pintype "passive"))
      (node (ref "C6") (pin "2") (pinfunction "2_2") (pintype "passive"))
      (node (ref "J1") (pin "5") (pinfunction "P5_5") (pintype "passive"))
      (node (ref "JP13") (pin "1") (pinfunction "1_1") (pintype "passive"))
      (node (ref "M1") (pin "1") (pinfunction "GND_1") (pintype "power_in"))
      (node (ref "M1") (pin "101") (pinfunction "GND_PAD_101") (pintype "power_in"))
      (node (ref "M1") (pin "15") (pinfunction "GND_15") (pintype "power_in"))
      (node (ref "M1") (pin "38") (pinfunction "GND_38") (pintype "power_in"))
      (node (ref "Q10") (pin "1") (pinfunction "E_1") (pintype "passive"))
      (node (ref "Q11") (pin "1") (pinfunction "E_1") (pintype "passive"))
      (node (ref "Q12") (pin "1") (pinfunction "E_1") (pintype "passive"))
      (node (ref "Q16") (pin "1") (pinfunction "E_1") (pintype "passive"))
      (node (ref "Q17") (pin "1") (pinfunction "E_1") (pintype "passive"))
      (node (ref "Q18") (pin "1") (pinfunction "E_1") (pintype "passive"))
      (node (ref "Q22") (pin "1") (pinfunction "E_1") (pintype "passive"))
      (node (ref "Q23") (pin "1") (pinfunction "E_1") (pintype "passive"))
      (node (ref "Q24") (pin "1") (pinfunction "E_1") (pintype "passive"))
      (node (ref "Q4") (pin "1") (pinfunction "E_1") (pintype "passive"))
      (node (ref "Q5") (pin "1") (pinfunction "E_1") (pintype "passive"))
      (node (ref "Q6") (pin "1") (pinfunction "E_1") (pintype "passive"))
      (node (ref "R13") (pin "1") (pinfunction "1_1") (pintype "passive"))
      (node (ref "R14") (pin "1") (pinfunction "1_1") (pintype "passive"))
      (node (ref "R15") (pin "1") (pinfunction "1_1") (pintype "passive"))
      (node (ref "R28") (pin "1") (pinfunction "1_1") (pintype "passive"))
      (node (ref "R29") (pin "1") (pinfunction "1_1") (pintype "passive"))
      (node (ref "R30") (pin "1") (pinfunction "1_1") (pintype "passive"))
      (node (ref "R45") (pin "1") (pinfunction "1_1") (pintype "passive"))
      (node (ref "R46") (pin "1") (pinfunction "1_1") (pintype "passive"))
      (node (ref "R47") (pin "1") (pinfunction "1_1") (pintype "passive"))
      (node (ref "R54") (pin "1") (pinfunction "1_1") (pintype "passive"))
      (node (ref "R61") (pin "1") (pinfunction "1_1") (pintype "passive"))
      (node (ref "R62") (pin "1") (pinfunction "1_1") (pintype "passive"))
      (node (ref "R63") (pin "1") (pinfunction "1_1") (pintype "passive"))
      (node (ref "R76") (pin "2") (pinfunction "2_2") (pintype "passive"))
      (node (ref "R77") (pin "2") (pinfunction "2_2") (pintype "passive"))
      (node (ref "R78") (pin "2") (pinfunction "2_2") (pintype "passive"))
      (node (ref "R79") (pin "2") (pinfunction "2_2") (pintype "passive"))
      (node (ref "R80") (pin "2") (pinfunction "2_2") (pintype "passive"))
      (node (ref "R81") (pin "2") (pinfunction "2_2") (pintype "passive"))
      (node (ref "R82") (pin "2") (pinfunction "2_2") (pintype "passive"))
      (node (ref "R83") (pin "2") (pinfunction "2_2") (pintype "passive"))
      (node (ref "R84") (pin "2") (pinfunction "2_2") (pintype "passive"))
      (node (ref "R85") (pin "2") (pinfunction "2_2") (pintype "passive"))
      (node (ref "R86") (pin "2") (pinfunction "2_2") (pintype "passive"))
      (node (ref "R87") (pin "2") (pinfunction "2_2") (pintype "passive"))
      (node (ref "R88") (pin "1") (pinfunction "1_1") (pintype "passive"))
      (node (ref "Reset1") (pin "2") (pinfunction "2_2") (pintype "passive"))
      (node (ref "U1") (pin "1") (pinfunction "GND_1") (pintype "passive"))
      (node (ref "flash1") (pin "1") (pinfunction "1_1") (pintype "passive"))
    )
    (net (code "22") (name "Net-(1-I)") (class "Default")
      (node (ref "1") (pin "1") (pinfunction "I_1") (pintype "power_in"))
      (node (ref "C1") (pin "2") (pinfunction "2_2") (pintype "passive"))
      (node (ref "C4") (pin "1") (pinfunction "1_1") (pintype "passive"))
      (node (ref "DIO1") (pin "2") (pinfunction "K_2") (pintype "passive"))
    )
    (net (code "23") (name "Net-(JP1-Pad1)") (class "Default")
      (node (ref "JP1") (pin "1") (pinfunction "1_1") (pintype "passive"))
      (node (ref "R2") (pin "1") (pinfunction "1_1") (pintype "passive"))
    )
    (net (code "24") (name "Net-(JP2-Pad1)") (class "Default")
      (node (ref "JP2") (pin "1") (pinfunction "1_1") (pintype "passive"))
      (node (ref "R4") (pin "1") (pinfunction "1_1") (pintype "passive"))
    )
    (net (code "25") (name "Net-(JP3-Pad1)") (class "Default")
      (node (ref "JP3") (pin "1") (pinfunction "1_1") (pintype "passive"))
      (node (ref "R6") (pin "1") (pinfunction "1_1") (pintype "passive"))
    )
    (net (code "26") (name "Net-(JP4-Pad1)") (class "Default")
      (node (ref "JP4") (pin "1") (pinfunction "1_1") (pintype "passive"))
      (node (ref "R17") (pin "1") (pinfunction "1_1") (pintype "passive"))
    )
    (net (code "27") (name "Net-(JP5-Pad1)") (class "Default")
      (node (ref "JP5") (pin "1") (pinfunction "1_1") (pintype "passive"))
      (node (ref "R19") (pin "1") (pinfunction "1_1") (pintype "passive"))
    )
    (net (code "28") (name "Net-(JP6-Pad1)") (class "Default")
      (node (ref "JP6") (pin "1") (pinfunction "1_1") (pintype "passive"))
      (node (ref "R21") (pin "1") (pinfunction "1_1") (pintype "passive"))
    )
    (net (code "29") (name "Net-(JP7-Pad1)") (class "Default")
      (node (ref "JP7") (pin "1") (pinfunction "1_1") (pintype "passive"))
      (node (ref "R34") (pin "1") (pinfunction "1_1") (pintype "passive"))
    )
    (net (code "30") (name "Net-(JP8-Pad1)") (class "Default")
      (node (ref "JP8") (pin "1") (pinfunction "1_1") (pintype "passive"))
      (node (ref "R36") (pin "1") (pinfunction "1_1") (pintype "passive"))
    )
    (net (code "31") (name "Net-(JP9-Pad1)") (class "Default")
      (node (ref "JP9") (pin "1") (pinfunction "1_1") (pintype "passive"))
      (node (ref "R38") (pin "1") (pinfunction "1_1") (pintype "passive"))
    )
    (net (code "32") (name "Net-(JP10-Pad1)") (class "Default")
      (node (ref "JP10") (pin "1") (pinfunction "1_1") (pintype "passive"))
      (node (ref "R49") (pin "1") (pinfunction "1_1") (pintype "passive"))
    )
    (net (code "33") (name "Net-(JP11-Pad1)") (class "Default")
      (node (ref "JP11") (pin "1") (pinfunction "1_1") (pintype "passive"))
      (node (ref "R51") (pin "1") (pinfunction "1_1") (pintype "passive"))
    )
    (net (code "34") (name "Net-(JP12-Pad1)") (class "Default")
      (node (ref "JP12") (pin "1") (pinfunction "1_1") (pintype "passive"))
      (node (ref "R53") (pin "1") (pinfunction "1_1") (pintype "passive"))
    )
    (net (code "35") (name "Net-(LED1-Pad2)") (class "Default")
      (node (ref "LED1") (pin "2") (pinfunction "2_2") (pintype "passive"))
      (node (ref "R54") (pin "2") (pinfunction "2_2") (pintype "passive"))
    )
    (net (code "36") (name "Net-(LED2-Pad2)") (class "Default")
      (node (ref "LED2") (pin "2") (pinfunction "2_2") (pintype "passive"))
      (node (ref "R76") (pin "1") (pinfunction "1_1") (pintype "passive"))
    )
    (net (code "37") (name "Net-(LED3-Pad2)") (class "Default")
      (node (ref "LED3") (pin "2") (pinfunction "2_2") (pintype "passive"))
      (node (ref "R77") (pin "1") (pinfunction "1_1") (pintype "passive"))
    )
    (net (code "38") (name "Net-(LED4-Pad2)") (class "Default")
      (node (ref "LED4") (pin "2") (pinfunction "2_2") (pintype "passive"))
      (node (ref "R78") (pin "1") (pinfunction "1_1") (pintype "passive"))
    )
    (net (code "39") (name "Net-(LED5-Pad2)") (class "Default")
      (node (ref "LED5") (pin "2") (pinfunction "2_2") (pintype "passive"))
      (node (ref "R79") (pin "1") (pinfunction "1_1") (pintype "passive"))
    )
    (net (code "40") (name "Net-(LED6-Pad2)") (class "Default")
      (node (ref "LED6") (pin "2") (pinfunction "2_2") (pintype "passive"))
      (node (ref "R80") (pin "1") (pinfunction "1_1") (pintype "passive"))
    )
    (net (code "41") (name "Net-(LED7-Pad2)") (class "Default")
      (node (ref "LED7") (pin "2") (pinfunction "2_2") (pintype "passive"))
      (node (ref "R81") (pin "1") (pinfunction "1_1") (pintype "passive"))
    )
    (net (code "42") (name "Net-(LED8-Pad2)") (class "Default")
      (node (ref "LED8") (pin "2") (pinfunction "2_2") (pintype "passive"))
      (node (ref "R82") (pin "1") (pinfunction "1_1") (pintype "passive"))
    )
    (net (code "43") (name "Net-(LED9-Pad2)") (class "Default")
      (node (ref "LED9") (pin "2") (pinfunction "2_2") (pintype "passive"))
      (node (ref "R83") (pin "1") (pinfunction "1_1") (pintype "passive"))
    )
    (net (code "44") (name "Net-(LED10-Pad2)") (class "Default")
      (node (ref "LED10") (pin "2") (pinfunction "2_2") (pintype "passive"))
      (node (ref "R84") (pin "1") (pinfunction "1_1") (pintype "passive"))
    )
    (net (code "45") (name "Net-(LED11-Pad2)") (class "Default")
      (node (ref "LED11") (pin "2") (pinfunction "2_2") (pintype "passive"))
      (node (ref "R85") (pin "1") (pinfunction "1_1") (pintype "passive"))
    )
    (net (code "46") (name "Net-(LED12-Pad2)") (class "Default")
      (node (ref "LED12") (pin "2") (pinfunction "2_2") (pintype "passive"))
      (node (ref "R86") (pin "1") (pinfunction "1_1") (pintype "passive"))
    )
    (net (code "47") (name "Net-(LED13-Pad2)") (class "Default")
      (node (ref "LED13") (pin "2") (pinfunction "2_2") (pintype "passive"))
      (node (ref "R87") (pin "1") (pinfunction "1_1") (pintype "passive"))
    )
    (net (code "48") (name "Net-(LED14-Pad2)") (class "Default")
      (node (ref "LED14") (pin "2") (pinfunction "2_2") (pintype "passive"))
      (node (ref "R88") (pin "2") (pinfunction "2_2") (pintype "passive"))
    )
    (net (code "49") (name "Net-(M1-EN)") (class "Default")
      (node (ref "M1") (pin "3") (pinfunction "EN_3") (pintype "power_in"))
      (node (ref "R32") (pin "2") (pinfunction "2_2") (pintype "passive"))
      (node (ref "Reset1") (pin "1") (pinfunction "1_1") (pintype "passive"))
    )
    (net (code "50") (name "Net-(M1-IO0)") (class "Default")
      (node (ref "M1") (pin "25") (pinfunction "IO0_25") (pintype "passive"))
      (node (ref "R31") (pin "1") (pinfunction "1_1") (pintype "passive"))
      (node (ref "flash1") (pin "2") (pinfunction "2_2") (pintype "passive"))
    )
    (net (code "51") (name "Net-(M1-IO27)") (class "Default")
      (node (ref "LED1") (pin "1") (pinfunction "1_1") (pintype "passive"))
      (node (ref "M1") (pin "12") (pinfunction "IO27_12") (pintype "passive"))
    )
    (net (code "52") (name "Net-(OPT1-A)") (class "Default")
      (node (ref "OPT1") (pin "1") (pinfunction "A_1") (pintype "passive"))
      (node (ref "R1") (pin "1") (pinfunction "1_1") (pintype "passive"))
    )
    (net (code "53") (name "Net-(OPT1-COLETOR)") (class "Default")
      (node (ref "OPT1") (pin "4") (pinfunction "COLETOR_4") (pintype "passive"))
      (node (ref "R2") (pin "2") (pinfunction "2_2") (pintype "passive"))
    )
    (net (code "54") (name "Net-(OPT1-EMISSOR)") (class "Default")
      (node (ref "OPT1") (pin "3") (pinfunction "EMISSOR_3") (pintype "passive"))
      (node (ref "Q1") (pin "1") (pinfunction "G_1") (pintype "passive"))
      (node (ref "R10") (pin "1") (pinfunction "1_1") (pintype "passive"))
    )
    (net (code "55") (name "Net-(OPT1-K)") (class "Default")
      (node (ref "OPT1") (pin "2") (pinfunction "K_2") (pintype "passive"))
      (node (ref "Q4") (pin "2") (pinfunction "C_2") (pintype "passive"))
    )
    (net (code "56") (name "Net-(OPT2-A)") (class "Default")
      (node (ref "OPT2") (pin "1") (pinfunction "A_1") (pintype "passive"))
      (node (ref "R3") (pin "1") (pinfunction "1_1") (pintype "passive"))
    )
    (net (code "57") (name "Net-(OPT2-COLETOR)") (class "Default")
      (node (ref "OPT2") (pin "4") (pinfunction "COLETOR_4") (pintype "passive"))
      (node (ref "R4") (pin "2") (pinfunction "2_2") (pintype "passive"))
    )
    (net (code "58") (name "Net-(OPT2-EMISSOR)") (class "Default")
      (node (ref "OPT2") (pin "3") (pinfunction "EMISSOR_3") (pintype "passive"))
      (node (ref "Q2") (pin "1") (pinfunction "G_1") (pintype "passive"))
      (node (ref "R11") (pin "1") (pinfunction "1_1") (pintype "passive"))
    )
    (net (code "59") (name "Net-(OPT2-K)") (class "Default")
      (node (ref "OPT2") (pin "2") (pinfunction "K_2") (pintype "passive"))
      (node (ref "Q5") (pin "2") (pinfunction "C_2") (pintype "passive"))
    )
    (net (code "60") (name "Net-(OPT3-A)") (class "Default")
      (node (ref "OPT3") (pin "1") (pinfunction "A_1") (pintype "passive"))
      (node (ref "R5") (pin "1") (pinfunction "1_1") (pintype "passive"))
    )
    (net (code "61") (name "Net-(OPT3-COLETOR)") (class "Default")
      (node (ref "OPT3") (pin "4") (pinfunction "COLETOR_4") (pintype "passive"))
      (node (ref "R6") (pin "2") (pinfunction "2_2") (pintype "passive"))
    )
    (net (code "62") (name "Net-(OPT3-EMISSOR)") (class "Default")
      (node (ref "OPT3") (pin "3") (pinfunction "EMISSOR_3") (pintype "passive"))
      (node (ref "Q3") (pin "1") (pinfunction "G_1") (pintype "passive"))
      (node (ref "R12") (pin "1") (pinfunction "1_1") (pintype "passive"))
    )
    (net (code "63") (name "Net-(OPT3-K)") (class "Default")
      (node (ref "OPT3") (pin "2") (pinfunction "K_2") (pintype "passive"))
      (node (ref "Q6") (pin "2") (pinfunction "C_2") (pintype "passive"))
    )
    (net (code "64") (name "Net-(OPT4-A)") (class "Default")
      (node (ref "OPT4") (pin "1") (pinfunction "A_1") (pintype "passive"))
      (node (ref "R16") (pin "1") (pinfunction "1_1") (pintype "passive"))
    )
    (net (code "65") (name "Net-(OPT4-COLETOR)") (class "Default")
      (node (ref "OPT4") (pin "4") (pinfunction "COLETOR_4") (pintype "passive"))
      (node (ref "R17") (pin "2") (pinfunction "2_2") (pintype "passive"))
    )
    (net (code "66") (name "Net-(OPT4-EMISSOR)") (class "Default")
      (node (ref "OPT4") (pin "3") (pinfunction "EMISSOR_3") (pintype "passive"))
      (node (ref "Q7") (pin "1") (pinfunction "G_1") (pintype "passive"))
      (node (ref "R25") (pin "1") (pinfunction "1_1") (pintype "passive"))
    )
    (net (code "67") (name "Net-(OPT4-K)") (class "Default")
      (node (ref "OPT4") (pin "2") (pinfunction "K_2") (pintype "passive"))
      (node (ref "Q10") (pin "2") (pinfunction "C_2") (pintype "passive"))
    )
    (net (code "68") (name "Net-(OPT5-A)") (class "Default")
      (node (ref "OPT5") (pin "1") (pinfunction "A_1") (pintype "passive"))
      (node (ref "R18") (pin "1") (pinfunction "1_1") (pintype "passive"))
    )
    (net (code "69") (name "Net-(OPT5-COLETOR)") (class "Default")
      (node (ref "OPT5") (pin "4") (pinfunction "COLETOR_4") (pintype "passive"))
      (node (ref "R19") (pin "2") (pinfunction "2_2") (pintype "passive"))
    )
    (net (code "70") (name "Net-(OPT5-EMISSOR)") (class "Default")
      (node (ref "OPT5") (pin "3") (pinfunction "EMISSOR_3") (pintype "passive"))
      (node (ref "Q8") (pin "1") (pinfunction "G_1") (pintype "passive"))
      (node (ref "R26") (pin "1") (pinfunction "1_1") (pintype "passive"))
    )
    (net (code "71") (name "Net-(OPT5-K)") (class "Default")
      (node (ref "OPT5") (pin "2") (pinfunction "K_2") (pintype "passive"))
      (node (ref "Q11") (pin "2") (pinfunction "C_2") (pintype "passive"))
    )
    (net (code "72") (name "Net-(OPT6-A)") (class "Default")
      (node (ref "OPT6") (pin "1") (pinfunction "A_1") (pintype "passive"))
      (node (ref "R20") (pin "1") (pinfunction "1_1") (pintype "passive"))
    )
    (net (code "73") (name "Net-(OPT6-COLETOR)") (class "Default")
      (node (ref "OPT6") (pin "4") (pinfunction "COLETOR_4") (pintype "passive"))
      (node (ref "R21") (pin "2") (pinfunction "2_2") (pintype "passive"))
    )
    (net (code "74") (name "Net-(OPT6-EMISSOR)") (class "Default")
      (node (ref "OPT6") (pin "3") (pinfunction "EMISSOR_3") (pintype "passive"))
      (node (ref "Q9") (pin "1") (pinfunction "G_1") (pintype "passive"))
      (node (ref "R27") (pin "1") (pinfunction "1_1") (pintype "passive"))
    )
    (net (code "75") (name "Net-(OPT6-K)") (class "Default")
      (node (ref "OPT6") (pin "2") (pinfunction "K_2") (pintype "passive"))
      (node (ref "Q12") (pin "2") (pinfunction "C_2") (pintype "passive"))
    )
    (net (code "76") (name "Net-(OPT7-A)") (class "Default")
      (node (ref "OPT7") (pin "1") (pinfunction "A_1") (pintype "passive"))
      (node (ref "R33") (pin "1") (pinfunction "1_1") (pintype "passive"))
    )
    (net (code "77") (name "Net-(OPT7-COLETOR)") (class "Default")
      (node (ref "OPT7") (pin "4") (pinfunction "COLETOR_4") (pintype "passive"))
      (node (ref "R34") (pin "2") (pinfunction "2_2") (pintype "passive"))
    )
    (net (code "78") (name "Net-(OPT7-EMISSOR)") (class "Default")
      (node (ref "OPT7") (pin "3") (pinfunction "EMISSOR_3") (pintype "passive"))
      (node (ref "Q13") (pin "1") (pinfunction "G_1") (pintype "passive"))
      (node (ref "R42") (pin "1") (pinfunction "1_1") (pintype "passive"))
    )
    (net (code "79") (name "Net-(OPT7-K)") (class "Default")
      (node (ref "OPT7") (pin "2") (pinfunction "K_2") (pintype "passive"))
      (node (ref "Q16") (pin "2") (pinfunction "C_2") (pintype "passive"))
    )
    (net (code "80") (name "Net-(OPT8-A)") (class "Default")
      (node (ref "OPT8") (pin "1") (pinfunction "A_1") (pintype "passive"))
      (node (ref "R35") (pin "1") (pinfunction "1_1") (pintype "passive"))
    )
    (net (code "81") (name "Net-(OPT8-COLETOR)") (class "Default")
      (node (ref "OPT8") (pin "4") (pinfunction "COLETOR_4") (pintype "passive"))
      (node (ref "R36") (pin "2") (pinfunction "2_2") (pintype "passive"))
    )
    (net (code "82") (name "Net-(OPT8-EMISSOR)") (class "Default")
      (node (ref "OPT8") (pin "3") (pinfunction "EMISSOR_3") (pintype "passive"))
      (node (ref "Q14") (pin "1") (pinfunction "G_1") (pintype "passive"))
      (node (ref "R43") (pin "1") (pinfunction "1_1") (pintype "passive"))
    )
    (net (code "83") (name "Net-(OPT8-K)") (class "Default")
      (node (ref "OPT8") (pin "2") (pinfunction "K_2") (pintype "passive"))
      (node (ref "Q17") (pin "2") (pinfunction "C_2") (pintype "passive"))
    )
    (net (code "84") (name "Net-(OPT9-A)") (class "Default")
      (node (ref "OPT9") (pin "1") (pinfunction "A_1") (pintype "passive"))
      (node (ref "R37") (pin "1") (pinfunction "1_1") (pintype "passive"))
    )
    (net (code "85") (name "Net-(OPT9-COLETOR)") (class "Default")
      (node (ref "OPT9") (pin "4") (pinfunction "COLETOR_4") (pintype "passive"))
      (node (ref "R38") (pin "2") (pinfunction "2_2") (pintype "passive"))
    )
    (net (code "86") (name "Net-(OPT9-EMISSOR)") (class "Default")
      (node (ref "OPT9") (pin "3") (pinfunction "EMISSOR_3") (pintype "passive"))
      (node (ref "Q15") (pin "1") (pinfunction "G_1") (pintype "passive"))
      (node (ref "R44") (pin "1") (pinfunction "1_1") (pintype "passive"))
    )
    (net (code "87") (name "Net-(OPT9-K)") (class "Default")
      (node (ref "OPT9") (pin "2") (pinfunction "K_2") (pintype "passive"))
      (node (ref "Q18") (pin "2") (pinfunction "C_2") (pintype "passive"))
    )
    (net (code "88") (name "Net-(OPT10-A)") (class "Default")
      (node (ref "OPT10") (pin "1") (pinfunction "A_1") (pintype "passive"))
      (node (ref "R48") (pin "1") (pinfunction "1_1") (pintype "passive"))
    )
    (net (code "89") (name "Net-(OPT10-COLETOR)") (class "Default")
      (node (ref "OPT10") (pin "4") (pinfunction "COLETOR_4") (pintype "passive"))
      (node (ref "R49") (pin "2") (pinfunction "2_2") (pintype "passive"))
    )
    (net (code "90") (name "Net-(OPT10-EMISSOR)") (class "Default")
      (node (ref "OPT10") (pin "3") (pinfunction "EMISSOR_3") (pintype "passive"))
      (node (ref "Q19") (pin "1") (pinfunction "G_1") (pintype "passive"))
      (node (ref "R58") (pin "1") (pinfunction "1_1") (pintype "passive"))
    )
    (net (code "91") (name "Net-(OPT10-K)") (class "Default")
      (node (ref "OPT10") (pin "2") (pinfunction "K_2") (pintype "passive"))
      (node (ref "Q22") (pin "2") (pinfunction "C_2") (pintype "passive"))
    )
    (net (code "92") (name "Net-(OPT11-A)") (class "Default")
      (node (ref "OPT11") (pin "1") (pinfunction "A_1") (pintype "passive"))
      (node (ref "R50") (pin "1") (pinfunction "1_1") (pintype "passive"))
    )
    (net (code "93") (name "Net-(OPT11-COLETOR)") (class "Default")
      (node (ref "OPT11") (pin "4") (pinfunction "COLETOR_4") (pintype "passive"))
      (node (ref "R51") (pin "2") (pinfunction "2_2") (pintype "passive"))
    )
    (net (code "94") (name "Net-(OPT11-EMISSOR)") (class "Default")
      (node (ref "OPT11") (pin "3") (pinfunction "EMISSOR_3") (pintype "passive"))
      (node (ref "Q20") (pin "1") (pinfunction "G_1") (pintype "passive"))
      (node (ref "R59") (pin "1") (pinfunction "1_1") (pintype "passive"))
    )
    (net (code "95") (name "Net-(OPT11-K)") (class "Default")
      (node (ref "OPT11") (pin "2") (pinfunction "K_2") (pintype "passive"))
      (node (ref "Q23") (pin "2") (pinfunction "C_2") (pintype "passive"))
    )
    (net (code "96") (name "Net-(OPT12-A)") (class "Default")
      (node (ref "OPT12") (pin "1") (pinfunction "A_1") (pintype "passive"))
      (node (ref "R52") (pin "1") (pinfunction "1_1") (pintype "passive"))
    )
    (net (code "97") (name "Net-(OPT12-COLETOR)") (class "Default")
      (node (ref "OPT12") (pin "4") (pinfunction "COLETOR_4") (pintype "passive"))
      (node (ref "R53") (pin "2") (pinfunction "2_2") (pintype "passive"))
    )
    (net (code "98") (name "Net-(OPT12-EMISSOR)") (class "Default")
      (node (ref "OPT12") (pin "3") (pinfunction "EMISSOR_3") (pintype "passive"))
      (node (ref "Q21") (pin "1") (pinfunction "G_1") (pintype "passive"))
      (node (ref "R60") (pin "1") (pinfunction "1_1") (pintype "passive"))
    )
    (net (code "99") (name "Net-(OPT12-K)") (class "Default")
      (node (ref "OPT12") (pin "2") (pinfunction "K_2") (pintype "passive"))
      (node (ref "Q24") (pin "2") (pinfunction "C_2") (pintype "passive"))
    )
    (net (code "100") (name "Net-(Q1-D)") (class "Default")
      (node (ref "JP1") (pin "2") (pinfunction "2_2") (pintype "passive"))
      (node (ref "Q1") (pin "2") (pinfunction "D_2") (pintype "passive"))
    )
    (net (code "101") (name "Net-(Q1-S)") (class "Default")
      (node (ref "JP1") (pin "3") (pinfunction "3_3") (pintype "passive"))
      (node (ref "Q1") (pin "3") (pinfunction "S_3") (pintype "passive"))
      (node (ref "R10") (pin "2") (pinfunction "2_2") (pintype "passive"))
    )
    (net (code "102") (name "Net-(Q2-D)") (class "Default")
      (node (ref "JP2") (pin "2") (pinfunction "2_2") (pintype "passive"))
      (node (ref "Q2") (pin "2") (pinfunction "D_2") (pintype "passive"))
    )
    (net (code "103") (name "Net-(Q2-S)") (class "Default")
      (node (ref "JP2") (pin "3") (pinfunction "3_3") (pintype "passive"))
      (node (ref "Q2") (pin "3") (pinfunction "S_3") (pintype "passive"))
      (node (ref "R11") (pin "2") (pinfunction "2_2") (pintype "passive"))
    )
    (net (code "104") (name "Net-(Q3-D)") (class "Default")
      (node (ref "JP3") (pin "2") (pinfunction "2_2") (pintype "passive"))
      (node (ref "Q3") (pin "2") (pinfunction "D_2") (pintype "passive"))
    )
    (net (code "105") (name "Net-(Q3-S)") (class "Default")
      (node (ref "JP3") (pin "3") (pinfunction "3_3") (pintype "passive"))
      (node (ref "Q3") (pin "3") (pinfunction "S_3") (pintype "passive"))
      (node (ref "R12") (pin "2") (pinfunction "2_2") (pintype "passive"))
    )
    (net (code "106") (name "Net-(Q4-B)") (class "Default")
      (node (ref "Q4") (pin "3") (pinfunction "B_3") (pintype "passive"))
      (node (ref "R7") (pin "2") (pinfunction "2_2") (pintype "passive"))
    )
    (net (code "107") (name "Net-(Q5-B)") (class "Default")
      (node (ref "Q5") (pin "3") (pinfunction "B_3") (pintype "passive"))
      (node (ref "R8") (pin "2") (pinfunction "2_2") (pintype "passive"))
    )
    (net (code "108") (name "Net-(Q6-B)") (class "Default")
      (node (ref "Q6") (pin "3") (pinfunction "B_3") (pintype "passive"))
      (node (ref "R9") (pin "2") (pinfunction "2_2") (pintype "passive"))
    )
    (net (code "109") (name "Net-(Q7-D)") (class "Default")
      (node (ref "JP4") (pin "2") (pinfunction "2_2") (pintype "passive"))
      (node (ref "Q7") (pin "2") (pinfunction "D_2") (pintype "passive"))
    )
    (net (code "110") (name "Net-(Q7-S)") (class "Default")
      (node (ref "JP4") (pin "3") (pinfunction "3_3") (pintype "passive"))
      (node (ref "Q7") (pin "3") (pinfunction "S_3") (pintype "passive"))
      (node (ref "R25") (pin "2") (pinfunction "2_2") (pintype "passive"))
    )
    (net (code "111") (name "Net-(Q8-D)") (class "Default")
      (node (ref "JP5") (pin "2") (pinfunction "2_2") (pintype "passive"))
      (node (ref "Q8") (pin "2") (pinfunction "D_2") (pintype "passive"))
    )
    (net (code "112") (name "Net-(Q8-S)") (class "Default")
      (node (ref "JP5") (pin "3") (pinfunction "3_3") (pintype "passive"))
      (node (ref "Q8") (pin "3") (pinfunction "S_3") (pintype "passive"))
      (node (ref "R26") (pin "2") (pinfunction "2_2") (pintype "passive"))
    )
    (net (code "113") (name "Net-(Q9-D)") (class "Default")
      (node (ref "JP6") (pin "2") (pinfunction "2_2") (pintype "passive"))
      (node (ref "Q9") (pin "2") (pinfunction "D_2") (pintype "passive"))
    )
    (net (code "114") (name "Net-(Q9-S)") (class "Default")
      (node (ref "JP6") (pin "3") (pinfunction "3_3") (pintype "passive"))
      (node (ref "Q9") (pin "3") (pinfunction "S_3") (pintype "passive"))
      (node (ref "R27") (pin "2") (pinfunction "2_2") (pintype "passive"))
    )
    (net (code "115") (name "Net-(Q10-B)") (class "Default")
      (node (ref "Q10") (pin "3") (pinfunction "B_3") (pintype "passive"))
      (node (ref "R22") (pin "2") (pinfunction "2_2") (pintype "passive"))
    )
    (net (code "116") (name "Net-(Q11-B)") (class "Default")
      (node (ref "Q11") (pin "3") (pinfunction "B_3") (pintype "passive"))
      (node (ref "R23") (pin "2") (pinfunction "2_2") (pintype "passive"))
    )
    (net (code "117") (name "Net-(Q12-B)") (class "Default")
      (node (ref "Q12") (pin "3") (pinfunction "B_3") (pintype "passive"))
      (node (ref "R24") (pin "2") (pinfunction "2_2") (pintype "passive"))
    )
    (net (code "118") (name "Net-(Q13-D)") (class "Default")
      (node (ref "JP7") (pin "2") (pinfunction "2_2") (pintype "passive"))
      (node (ref "Q13") (pin "2") (pinfunction "D_2") (pintype "passive"))
    )
    (net (code "119") (name "Net-(Q13-S)") (class "Default")
      (node (ref "JP7") (pin "3") (pinfunction "3_3") (pintype "passive"))
      (node (ref "Q13") (pin "3") (pinfunction "S_3") (pintype "passive"))
      (node (ref "R42") (pin "2") (pinfunction "2_2") (pintype "passive"))
    )
    (net (code "120") (name "Net-(Q14-D)") (class "Default")
      (node (ref "JP8") (pin "2") (pinfunction "2_2") (pintype "passive"))
      (node (ref "Q14") (pin "2") (pinfunction "D_2") (pintype "passive"))
    )
    (net (code "121") (name "Net-(Q14-S)") (class "Default")
      (node (ref "JP8") (pin "3") (pinfunction "3_3") (pintype "passive"))
      (node (ref "Q14") (pin "3") (pinfunction "S_3") (pintype "passive"))
      (node (ref "R43") (pin "2") (pinfunction "2_2") (pintype "passive"))
    )
    (net (code "122") (name "Net-(Q15-D)") (class "Default")
      (node (ref "JP9") (pin "2") (pinfunction "2_2") (pintype "passive"))
      (node (ref "Q15") (pin "2") (pinfunction "D_2") (pintype "passive"))
    )
    (net (code "123") (name "Net-(Q15-S)") (class "Default")
      (node (ref "JP9") (pin "3") (pinfunction "3_3") (pintype "passive"))
      (node (ref "Q15") (pin "3") (pinfunction "S_3") (pintype "passive"))
      (node (ref "R44") (pin "2") (pinfunction "2_2") (pintype "passive"))
    )
    (net (code "124") (name "Net-(Q16-B)") (class "Default")
      (node (ref "Q16") (pin "3") (pinfunction "B_3") (pintype "passive"))
      (node (ref "R39") (pin "2") (pinfunction "2_2") (pintype "passive"))
    )
    (net (code "125") (name "Net-(Q17-B)") (class "Default")
      (node (ref "Q17") (pin "3") (pinfunction "B_3") (pintype "passive"))
      (node (ref "R40") (pin "2") (pinfunction "2_2") (pintype "passive"))
    )
    (net (code "126") (name "Net-(Q18-B)") (class "Default")
      (node (ref "Q18") (pin "3") (pinfunction "B_3") (pintype "passive"))
      (node (ref "R41") (pin "2") (pinfunction "2_2") (pintype "passive"))
    )
    (net (code "127") (name "Net-(Q19-D)") (class "Default")
      (node (ref "JP10") (pin "2") (pinfunction "2_2") (pintype "passive"))
      (node (ref "Q19") (pin "2") (pinfunction "D_2") (pintype "passive"))
    )
    (net (code "128") (name "Net-(Q19-S)") (class "Default")
      (node (ref "JP10") (pin "3") (pinfunction "3_3") (pintype "passive"))
      (node (ref "Q19") (pin "3") (pinfunction "S_3") (pintype "passive"))
      (node (ref "R58") (pin "2") (pinfunction "2_2") (pintype "passive"))
    )
    (net (code "129") (name "Net-(Q20-D)") (class "Default")
      (node (ref "JP11") (pin "2") (pinfunction "2_2") (pintype "passive"))
      (node (ref "Q20") (pin "2") (pinfunction "D_2") (pintype "passive"))
    )
    (net (code "130") (name "Net-(Q20-S)") (class "Default")
      (node (ref "JP11") (pin "3") (pinfunction "3_3") (pintype "passive"))
      (node (ref "Q20") (pin "3") (pinfunction "S_3") (pintype "passive"))
      (node (ref "R59") (pin "2") (pinfunction "2_2") (pintype "passive"))
    )
    (net (code "131") (name "Net-(Q21-D)") (class "Default")
      (node (ref "JP12") (pin "2") (pinfunction "2_2") (pintype "passive"))
      (node (ref "Q21") (pin "2") (pinfunction "D_2") (pintype "passive"))
    )
    (net (code "132") (name "Net-(Q21-S)") (class "Default")
      (node (ref "JP12") (pin "3") (pinfunction "3_3") (pintype "passive"))
      (node (ref "Q21") (pin "3") (pinfunction "S_3") (pintype "passive"))
      (node (ref "R60") (pin "2") (pinfunction "2_2") (pintype "passive"))
    )
    (net (code "133") (name "Net-(Q22-B)") (class "Default")
      (node (ref "Q22") (pin "3") (pinfunction "B_3") (pintype "passive"))
      (node (ref "R55") (pin "2") (pinfunction "2_2") (pintype "passive"))
    )
    (net (code "134") (name "Net-(Q23-B)") (class "Default")
      (node (ref "Q23") (pin "3") (pinfunction "B_3") (pintype "passive"))
      (node (ref "R56") (pin "2") (pinfunction "2_2") (pintype "passive"))
    )
    (net (code "135") (name "Net-(Q24-B)") (class "Default")
      (node (ref "Q24") (pin "3") (pinfunction "B_3") (pintype "passive"))
      (node (ref "R57") (pin "2") (pinfunction "2_2") (pintype "passive"))
    )
    (net (code "136") (name "Net-(Q25-B)") (class "Default")
      (node (ref "Q25") (pin "3") (pinfunction "B_3") (pintype "passive"))
      (node (ref "R64") (pin "2") (pinfunction "2_2") (pintype "passive"))
    )
    (net (code "137") (name "Net-(Q25-E)") (class "Default")
      (node (ref "LED2") (pin "1") (pinfunction "1_1") (pintype "passive"))
      (node (ref "Q25") (pin "1") (pinfunction "E_1") (pintype "passive"))
    )
    (net (code "138") (name "Net-(Q26-B)") (class "Default")
      (node (ref "Q26") (pin "3") (pinfunction "B_3") (pintype "passive"))
      (node (ref "R65") (pin "2") (pinfunction "2_2") (pintype "passive"))
    )
    (net (code "139") (name "Net-(Q26-E)") (class "Default")
      (node (ref "LED3") (pin "1") (pinfunction "1_1") (pintype "passive"))
      (node (ref "Q26") (pin "1") (pinfunction "E_1") (pintype "passive"))
    )
    (net (code "140") (name "Net-(Q27-B)") (class "Default")
      (node (ref "Q27") (pin "3") (pinfunction "B_3") (pintype "passive"))
      (node (ref "R66") (pin "2") (pinfunction "2_2") (pintype "passive"))
    )
    (net (code "141") (name "Net-(Q27-E)") (class "Default")
      (node (ref "LED4") (pin "1") (pinfunction "1_1") (pintype "passive"))
      (node (ref "Q27") (pin "1") (pinfunction "E_1") (pintype "passive"))
    )
    (net (code "142") (name "Net-(Q28-B)") (class "Default")
      (node (ref "Q28") (pin "3") (pinfunction "B_3") (pintype "passive"))
      (node (ref "R67") (pin "2") (pinfunction "2_2") (pintype "passive"))
    )
    (net (code "143") (name "Net-(Q28-E)") (class "Default")
      (node (ref "LED5") (pin "1") (pinfunction "1_1") (pintype "passive"))
      (node (ref "Q28") (pin "1") (pinfunction "E_1") (pintype "passive"))
    )
    (net (code "144") (name "Net-(Q29-B)") (class "Default")
      (node (ref "Q29") (pin "3") (pinfunction "B_3") (pintype "passive"))
      (node (ref "R68") (pin "2") (pinfunction "2_2") (pintype "passive"))
    )
    (net (code "145") (name "Net-(Q29-E)") (class "Default")
      (node (ref "LED6") (pin "1") (pinfunction "1_1") (pintype "passive"))
      (node (ref "Q29") (pin "1") (pinfunction "E_1") (pintype "passive"))
    )
    (net (code "146") (name "Net-(Q30-B)") (class "Default")
      (node (ref "Q30") (pin "3") (pinfunction "B_3") (pintype "passive"))
      (node (ref "R69") (pin "2") (pinfunction "2_2") (pintype "passive"))
    )
    (net (code "147") (name "Net-(Q30-E)") (class "Default")
      (node (ref "LED7") (pin "1") (pinfunction "1_1") (pintype "passive"))
      (node (ref "Q30") (pin "1") (pinfunction "E_1") (pintype "passive"))
    )
    (net (code "148") (name "Net-(Q31-B)") (class "Default")
      (node (ref "Q31") (pin "3") (pinfunction "B_3") (pintype "passive"))
      (node (ref "R70") (pin "2") (pinfunction "2_2") (pintype "passive"))
    )
    (net (code "149") (name "Net-(Q31-E)") (class "Default")
      (node (ref "LED8") (pin "1") (pinfunction "1_1") (pintype "passive"))
      (node (ref "Q31") (pin "1") (pinfunction "E_1") (pintype "passive"))
    )
    (net (code "150") (name "Net-(Q32-B)") (class "Default")
      (node (ref "Q32") (pin "3") (pinfunction "B_3") (pintype "passive"))
      (node (ref "R71") (pin "2") (pinfunction "2_2") (pintype "passive"))
    )
    (net (code "151") (name "Net-(Q32-E)") (class "Default")
      (node (ref "LED9") (pin "1") (pinfunction "1_1") (pintype "passive"))
      (node (ref "Q32") (pin "1") (pinfunction "E_1") (pintype "passive"))
    )
    (net (code "152") (name "Net-(Q33-B)") (class "Default")
      (node (ref "Q33") (pin "3") (pinfunction "B_3") (pintype "passive"))
      (node (ref "R72") (pin "2") (pinfunction "2_2") (pintype "passive"))
    )
    (net (code "153") (name "Net-(Q33-E)") (class "Default")
      (node (ref "LED10") (pin "1") (pinfunction "1_1") (pintype "passive"))
      (node (ref "Q33") (pin "1") (pinfunction "E_1") (pintype "passive"))
    )
    (net (code "154") (name "Net-(Q34-B)") (class "Default")
      (node (ref "Q34") (pin "3") (pinfunction "B_3") (pintype "passive"))
      (node (ref "R73") (pin "2") (pinfunction "2_2") (pintype "passive"))
    )
    (net (code "155") (name "Net-(Q34-E)") (class "Default")
      (node (ref "LED11") (pin "1") (pinfunction "1_1") (pintype "passive"))
      (node (ref "Q34") (pin "1") (pinfunction "E_1") (pintype "passive"))
    )
    (net (code "156") (name "Net-(Q35-B)") (class "Default")
      (node (ref "Q35") (pin "3") (pinfunction "B_3") (pintype "passive"))
      (node (ref "R74") (pin "2") (pinfunction "2_2") (pintype "passive"))
    )
    (net (code "157") (name "Net-(Q35-E)") (class "Default")
      (node (ref "LED12") (pin "1") (pinfunction "1_1") (pintype "passive"))
      (node (ref "Q35") (pin "1") (pinfunction "E_1") (pintype "passive"))
    )
    (net (code "158") (name "Net-(Q36-B)") (class "Default")
      (node (ref "Q36") (pin "3") (pinfunction "B_3") (pintype "passive"))
      (node (ref "R75") (pin "2") (pinfunction "2_2") (pintype "passive"))
    )
    (net (code "159") (name "Net-(Q36-E)") (class "Default")
      (node (ref "LED13") (pin "1") (pinfunction "1_1") (pintype "passive"))
      (node (ref "Q36") (pin "1") (pinfunction "E_1") (pintype "passive"))
    )
    (net (code "160") (name "unconnected-(J1-P4-Pad4)") (class "Default")
      (node (ref "J1") (pin "4") (pinfunction "P4_4") (pintype "passive"))
    )
    (net (code "161") (name "unconnected-(M1-CLK-Pad20)") (class "Default")
      (node (ref "M1") (pin "20") (pinfunction "CLK_20") (pintype "passive"))
    )
    (net (code "162") (name "unconnected-(M1-CMD-Pad19)") (class "Default")
      (node (ref "M1") (pin "19") (pinfunction "CMD_19") (pintype "passive"))
    )
    (net (code "163") (name "unconnected-(M1-IO16-Pad27)") (class "Default")
      (node (ref "M1") (pin "27") (pinfunction "IO16_27") (pintype "passive"))
    )
    (net (code "164") (name "unconnected-(M1-IO32-Pad8)") (class "Default")
      (node (ref "M1") (pin "8") (pinfunction "IO32_8") (pintype "passive"))
    )
    (net (code "165") (name "unconnected-(M1-IO33-Pad9)") (class "Default")
      (node (ref "M1") (pin "9") (pinfunction "IO33_9") (pintype "passive"))
    )
    (net (code "166") (name "unconnected-(M1-IO34-Pad6)") (class "Default")
      (node (ref "M1") (pin "6") (pinfunction "IO34_6") (pintype "passive"))
    )
    (net (code "167") (name "unconnected-(M1-IO35-Pad7)") (class "Default")
      (node (ref "M1") (pin "7") (pinfunction "IO35_7") (pintype "passive"))
    )
    (net (code "168") (name "unconnected-(M1-NC-Pad32)") (class "Default")
      (node (ref "M1") (pin "32") (pinfunction "NC_32") (pintype "passive"))
    )
    (net (code "169") (name "unconnected-(M1-SD0-Pad21)") (class "Default")
      (node (ref "M1") (pin "21") (pinfunction "SD0_21") (pintype "passive"))
    )
    (net (code "170") (name "unconnected-(M1-SD1-Pad22)") (class "Default")
      (node (ref "M1") (pin "22") (pinfunction "SD1_22") (pintype "passive"))
    )
    (net (code "171") (name "unconnected-(M1-SD2-Pad17)") (class "Default")
      (node (ref "M1") (pin "17") (pinfunction "SD2_17") (pintype "passive"))
    )
    (net (code "172") (name "unconnected-(M1-SD3-Pad18)") (class "Default")
      (node (ref "M1") (pin "18") (pinfunction "SD3_18") (pintype "passive"))
    )
    (net (code "173") (name "unconnected-(M1-SENSOR_VN-Pad5)") (class "Default")
      (node (ref "M1") (pin "5") (pinfunction "SENSOR_VN_5") (pintype "passive"))
    )
    (net (code "174") (name "unconnected-(M1-SENSOR_VP-Pad4)") (class "Default")
      (node (ref "M1") (pin "4") (pinfunction "SENSOR_VP_4") (pintype "passive"))
    )
  )
)
